# Pinscape_Pico_Expansion_Board_-_DIY_Frie.net
KiCad netlist of a schematic drawn in EAGLE
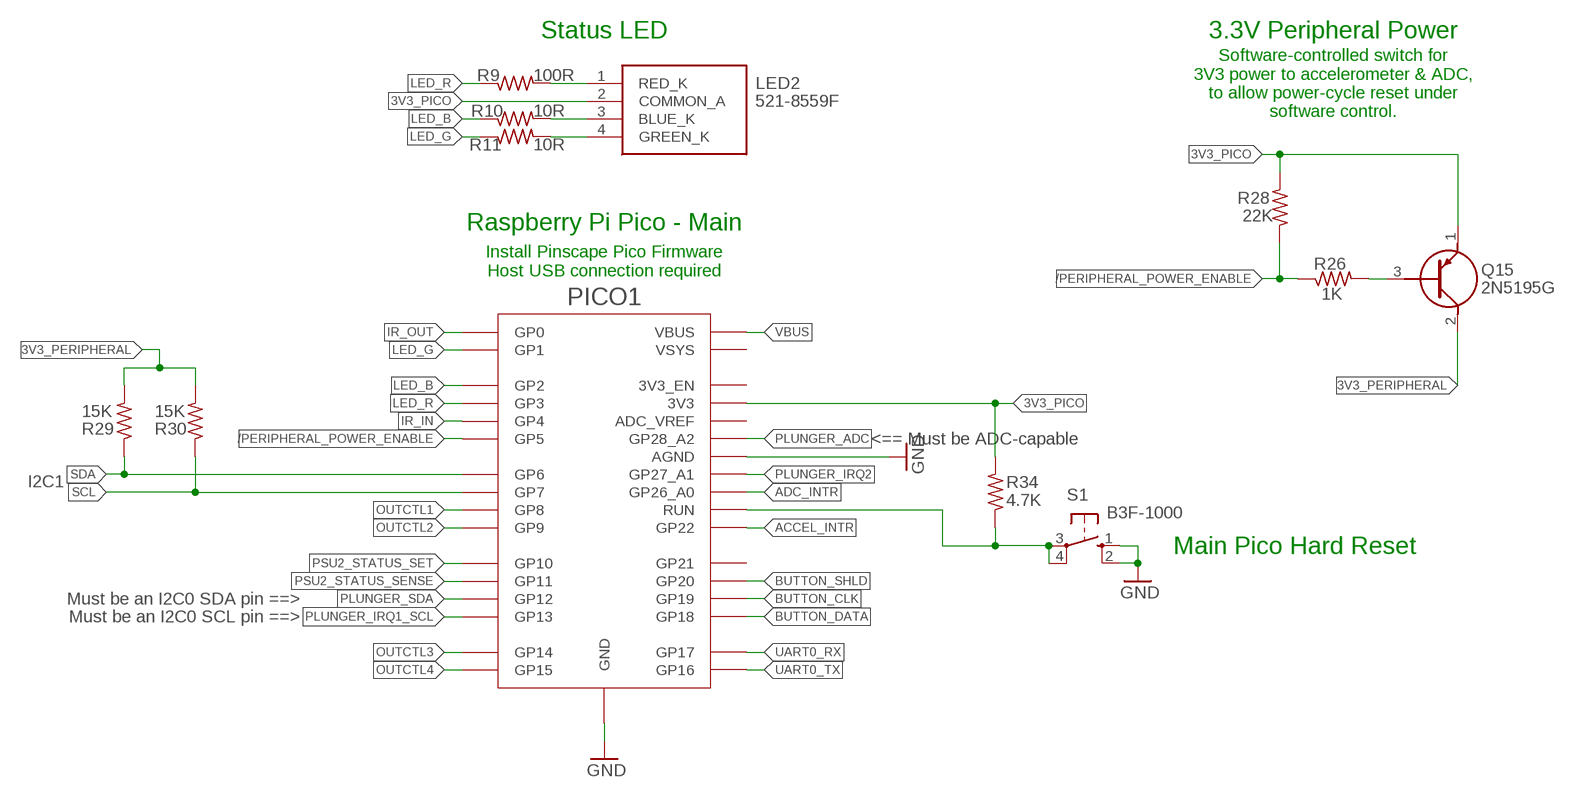
[diagram p0: schematic, sheet 1]
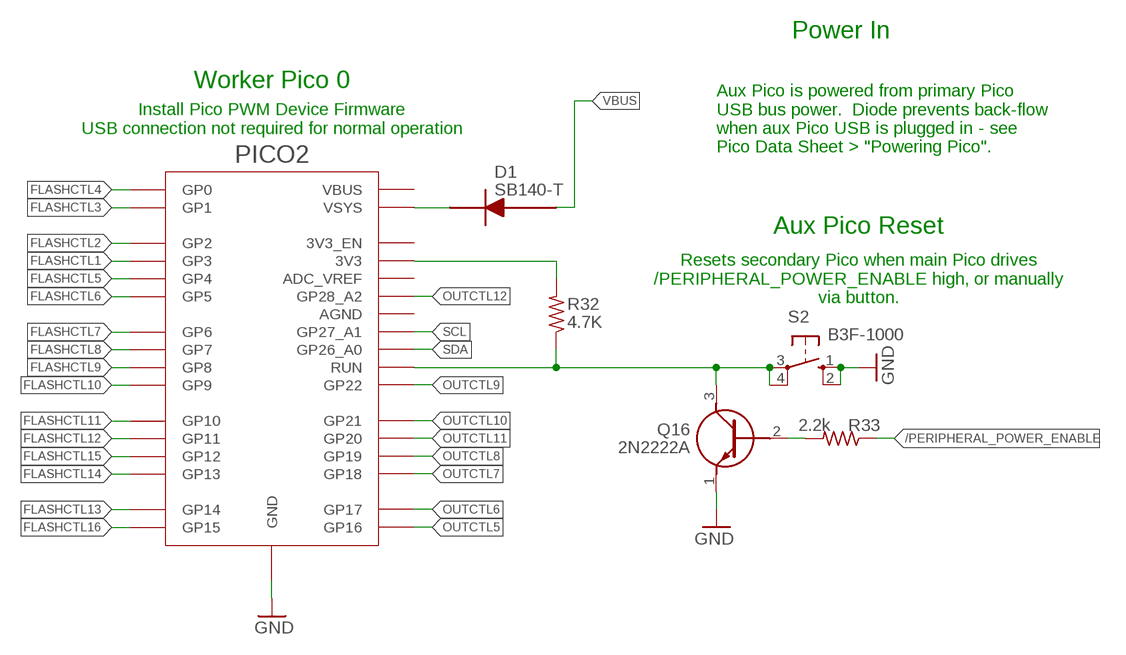
[diagram p1: schematic, sheet 2]
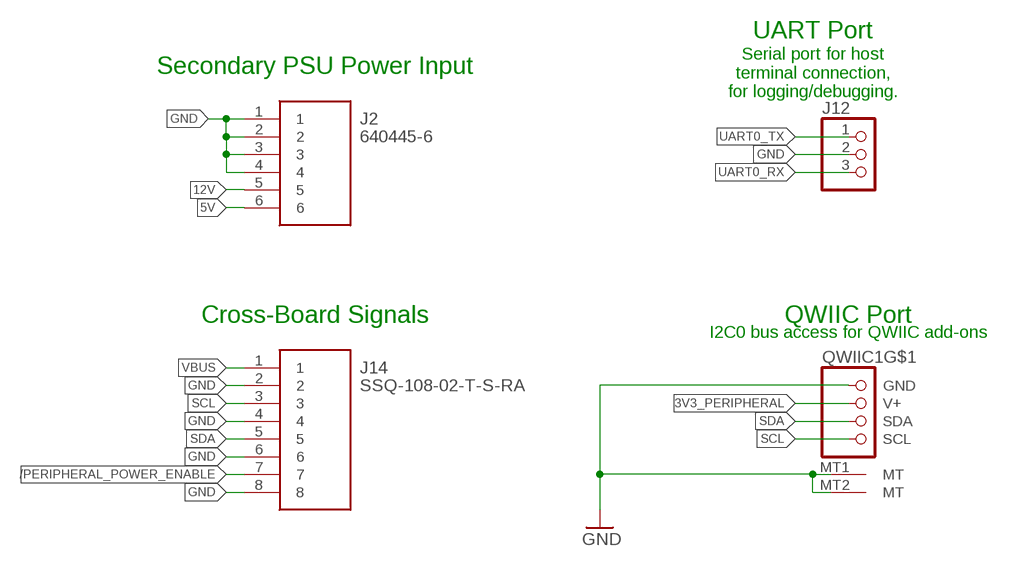
[diagram p2: schematic, sheet 3]
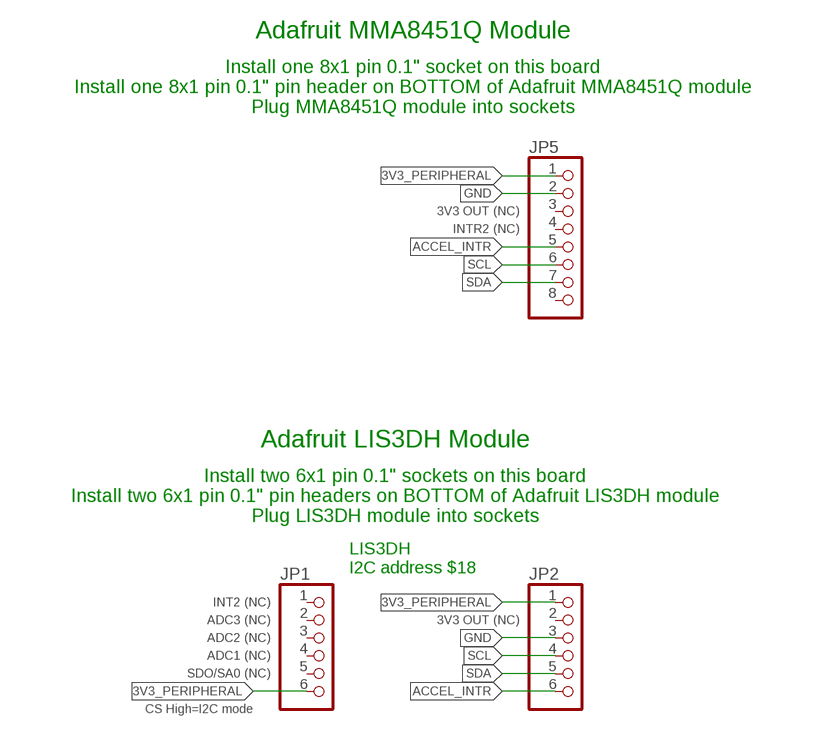
[diagram p3: schematic, sheet 4]
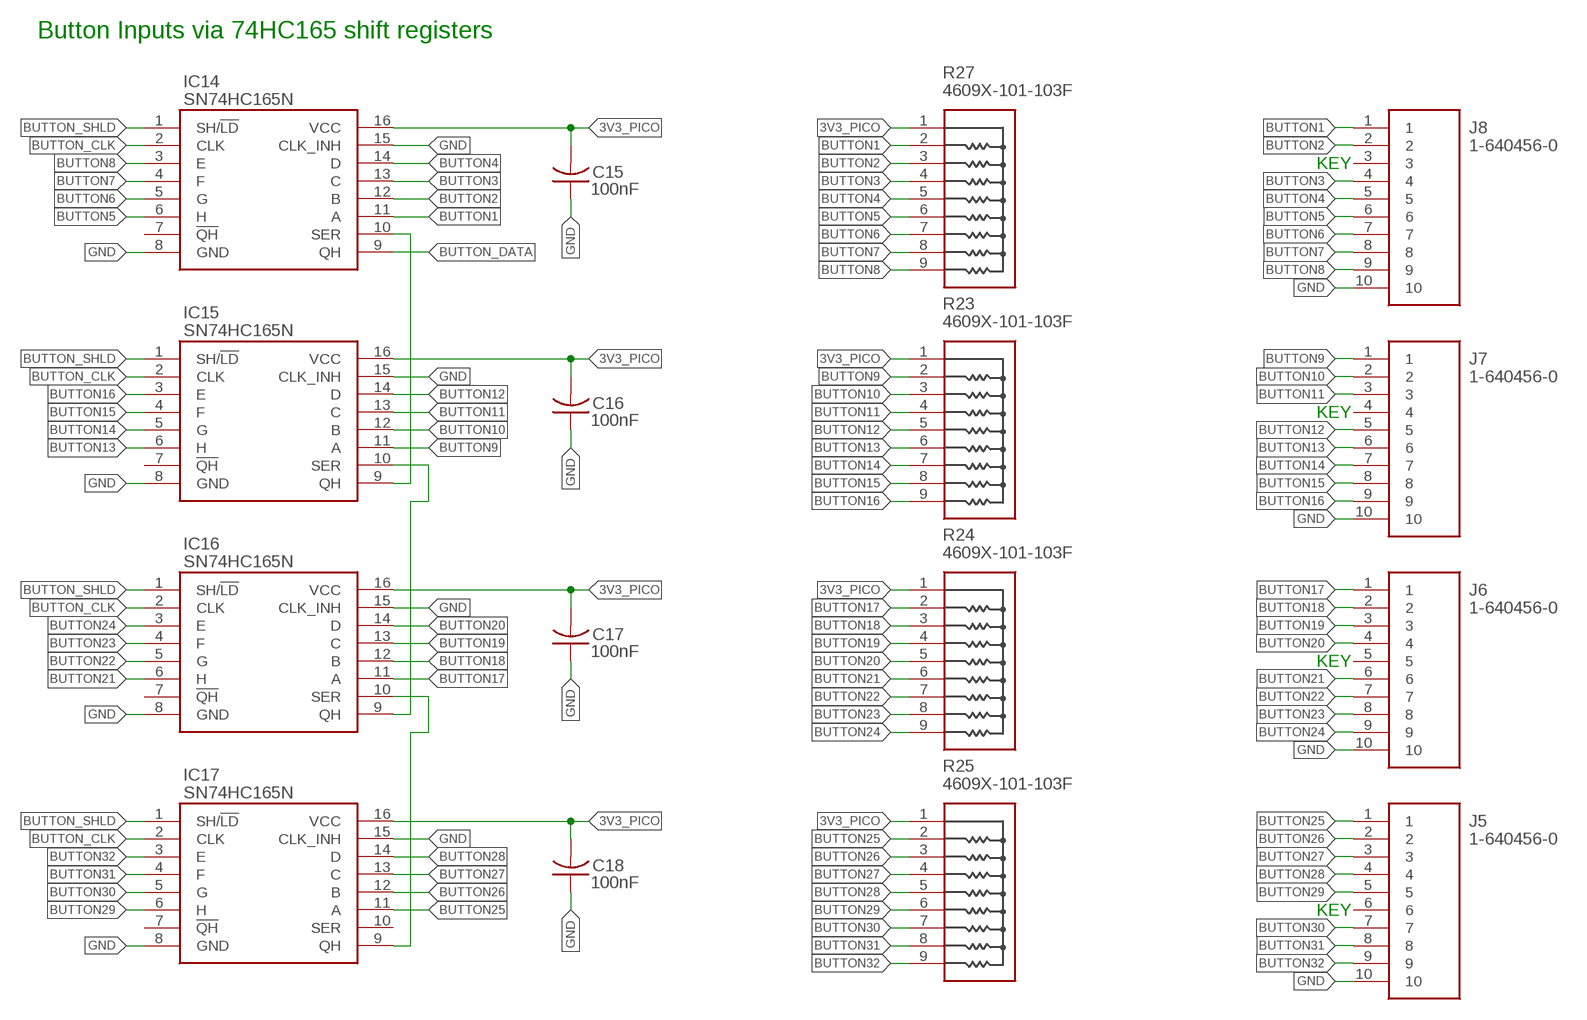
[diagram p4: schematic, sheet 5]
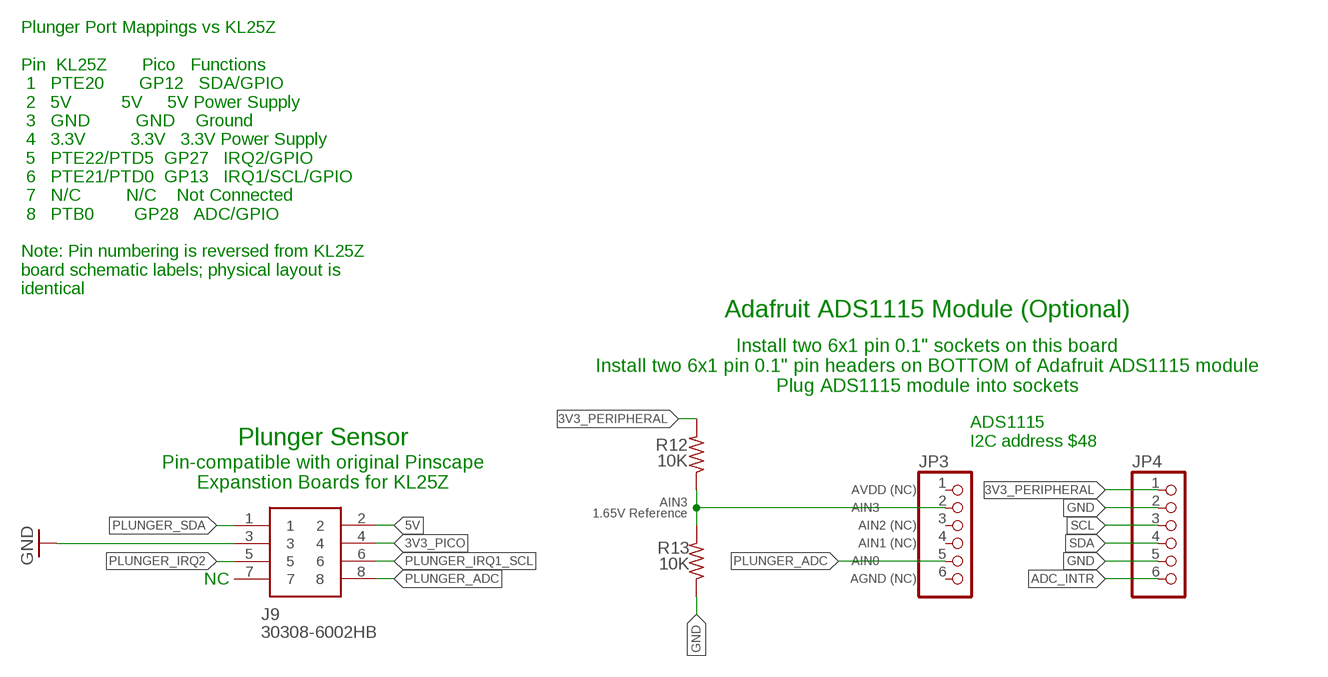
[diagram p5: schematic, sheet 6]
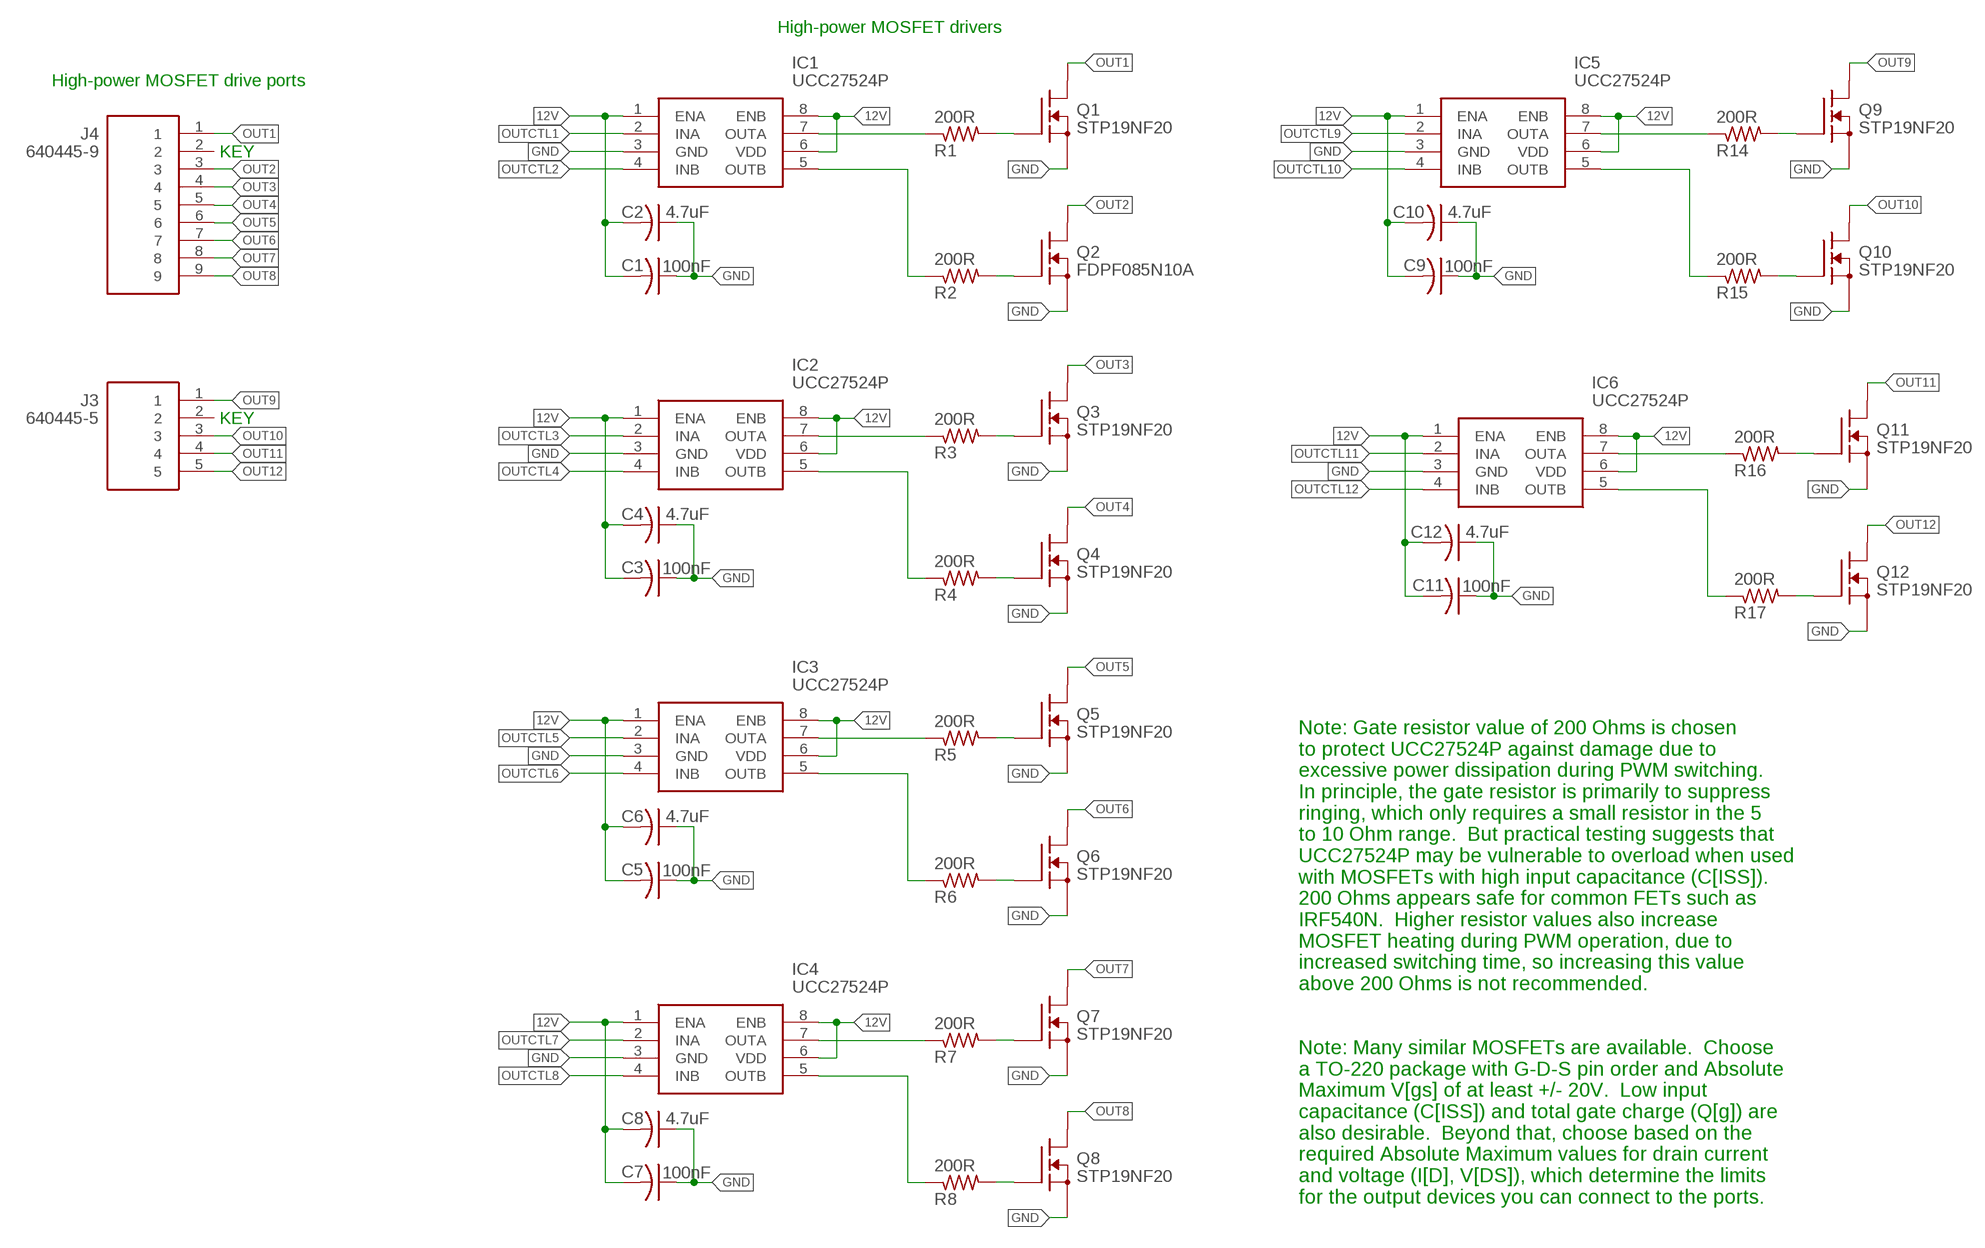
[diagram p6: schematic, sheet 7]
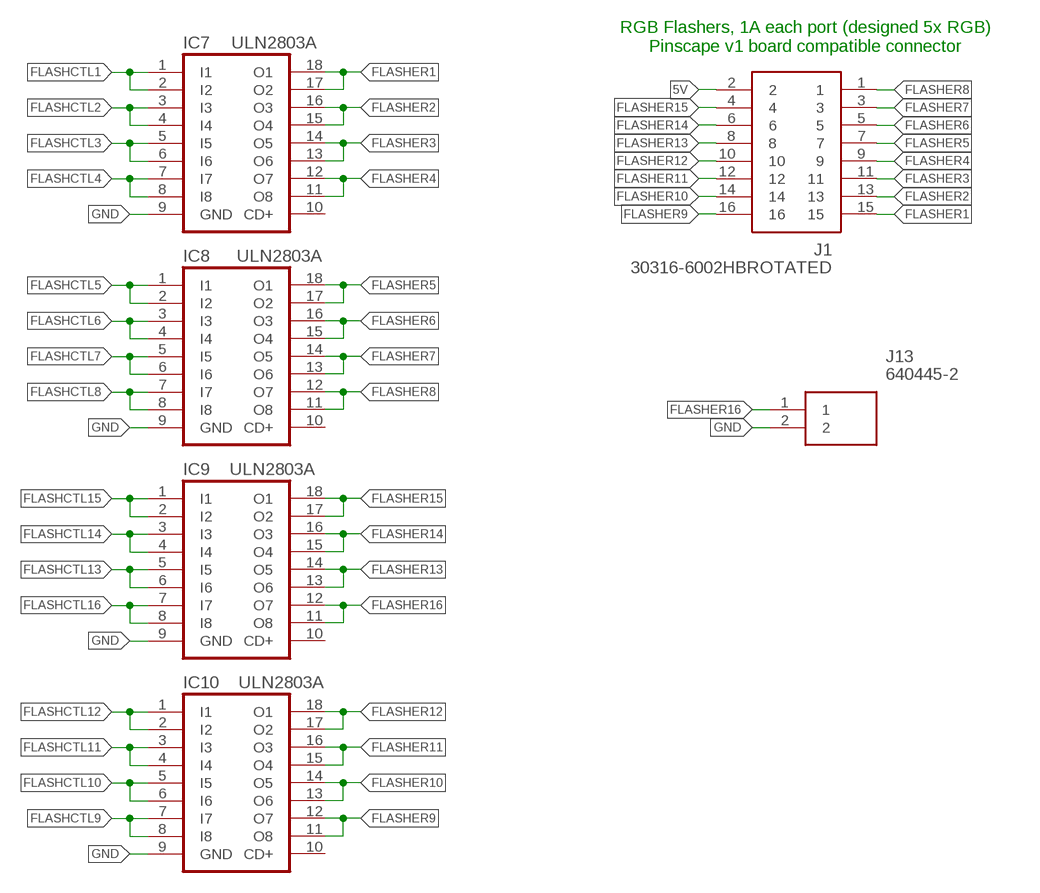
[diagram p7: schematic, sheet 8]
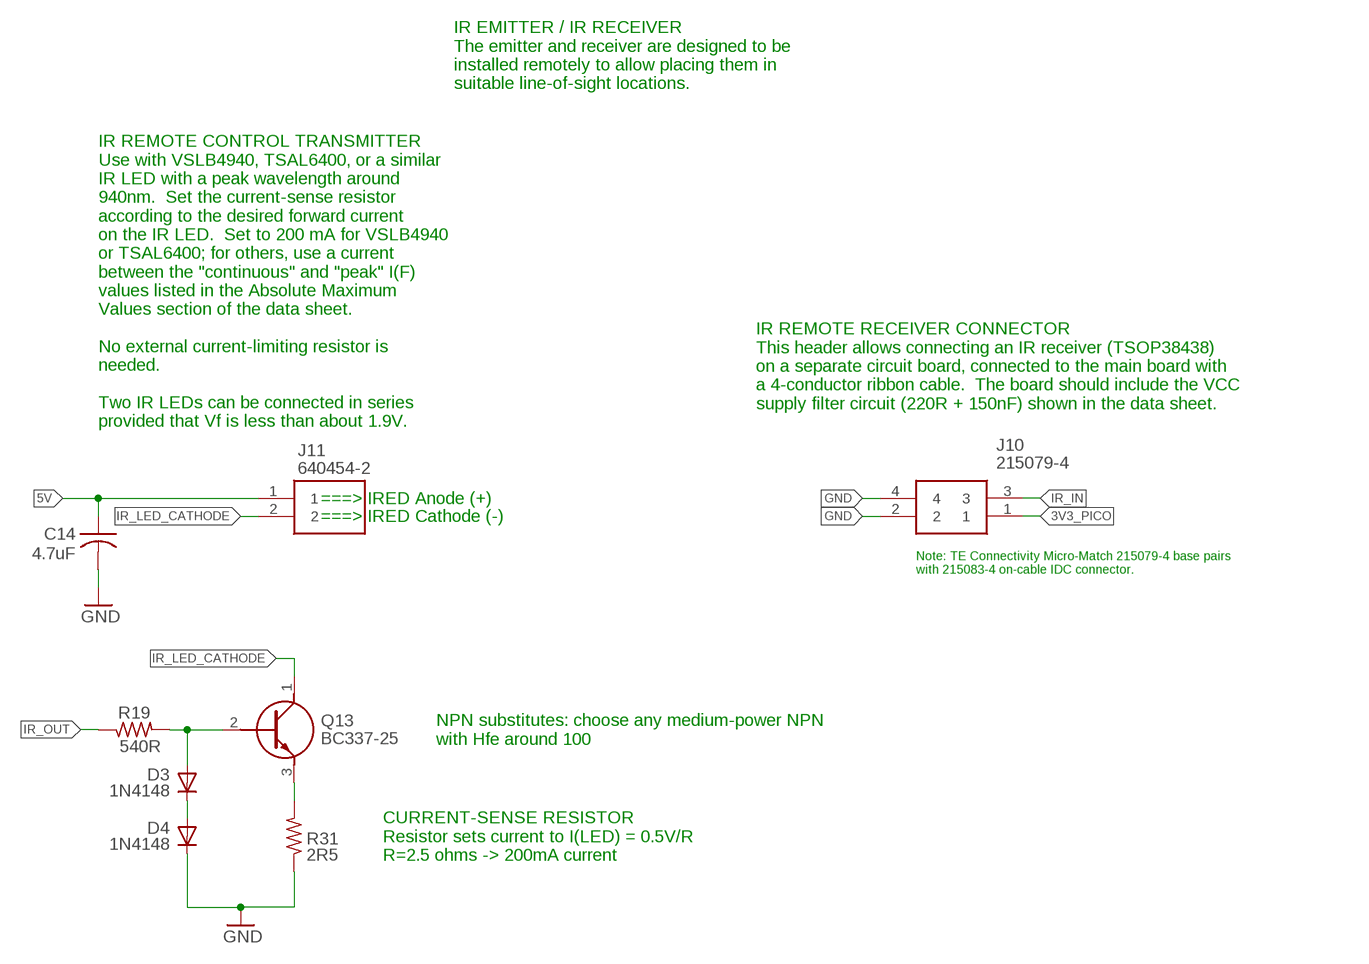
[diagram p8: schematic, sheet 9]
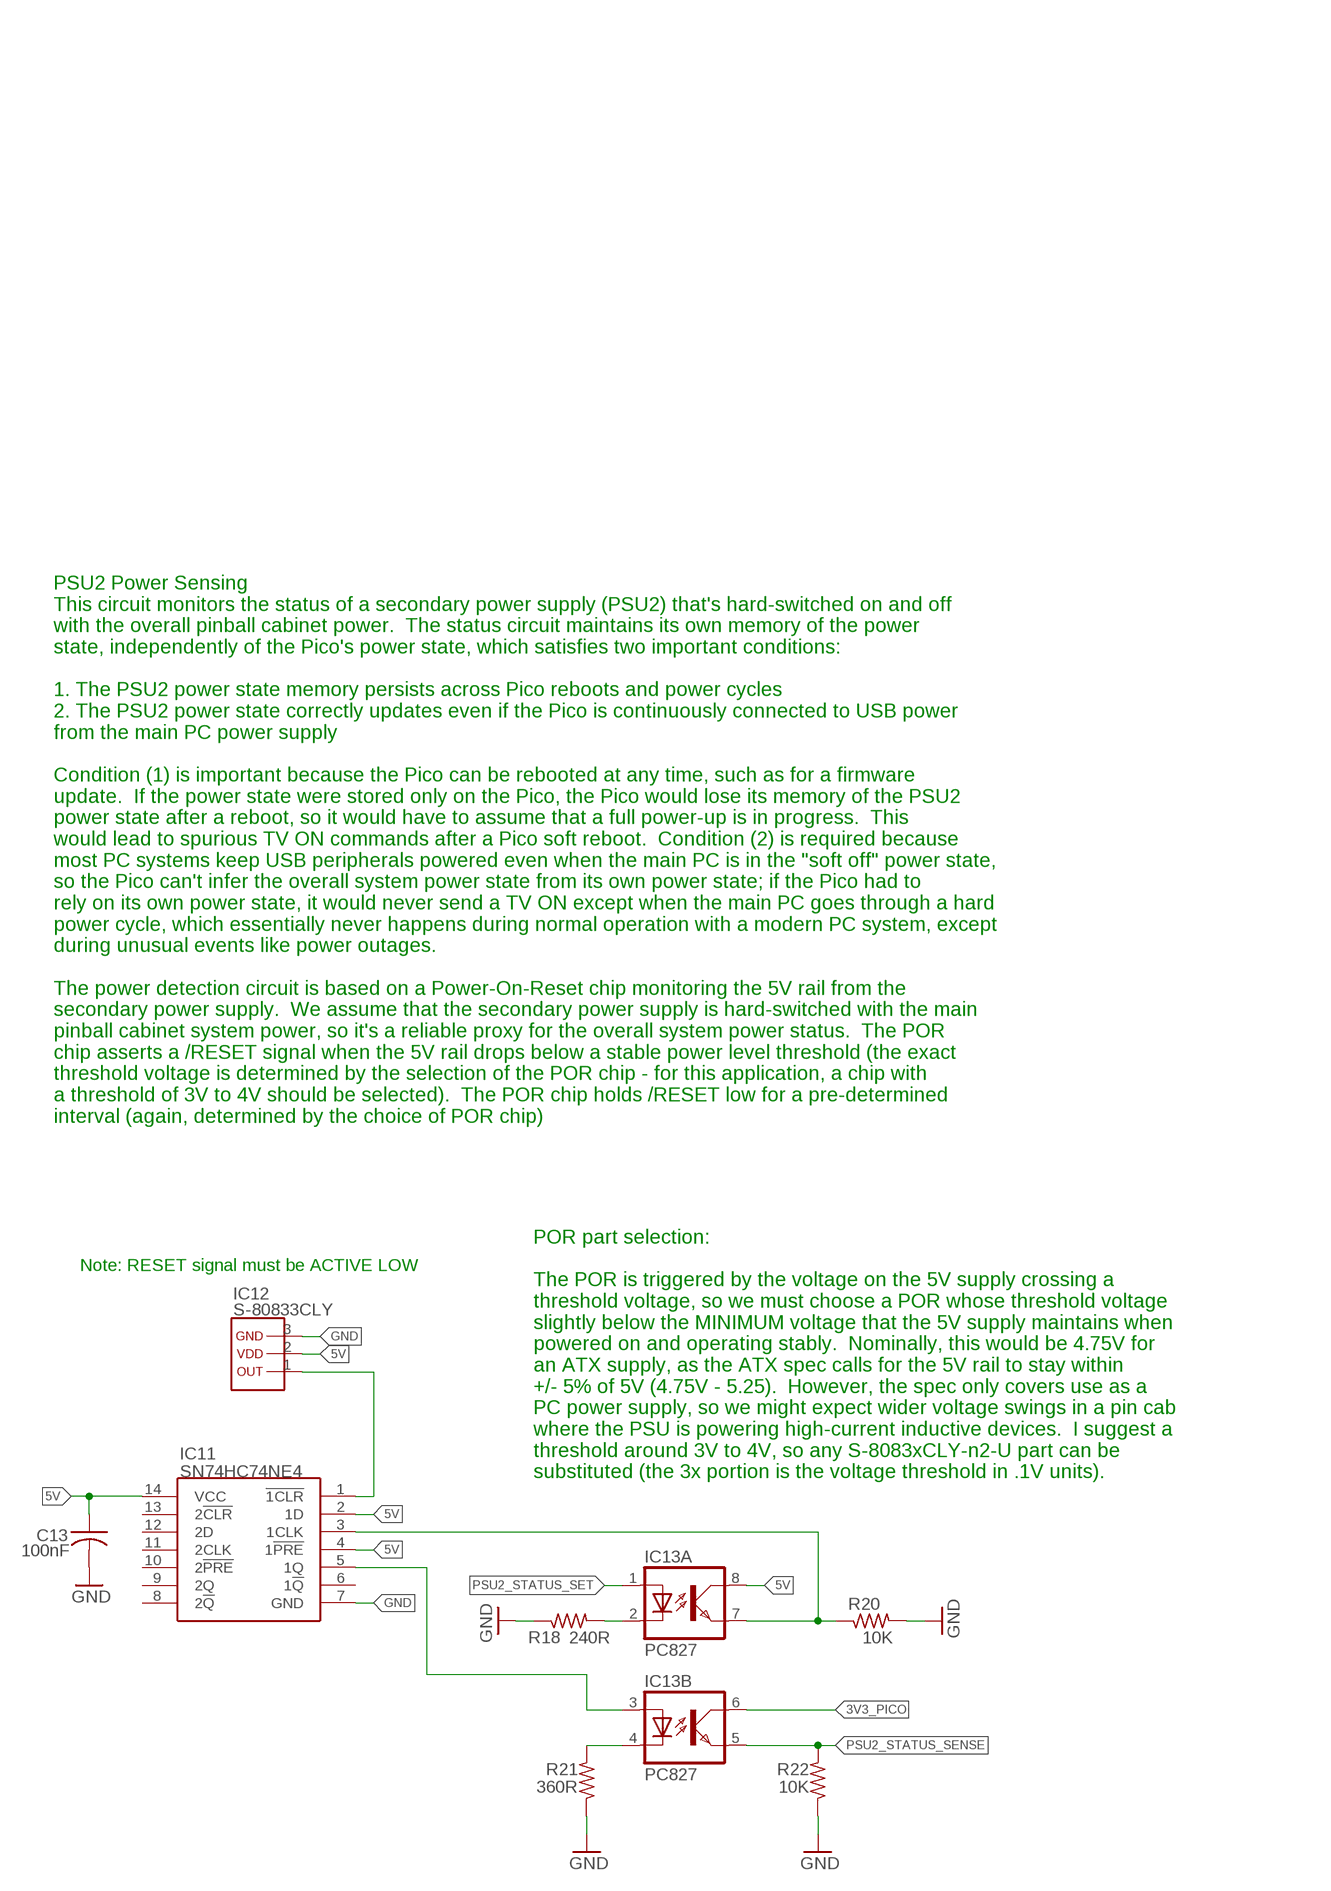
[diagram p9: schematic, sheet 10]
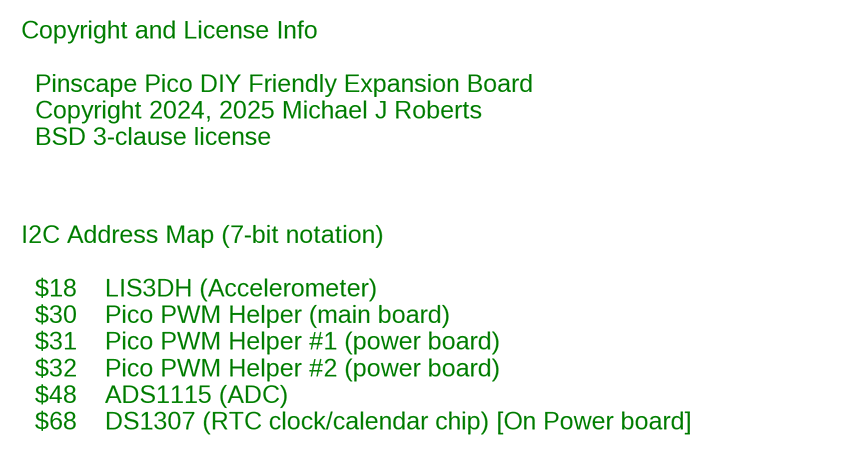
[diagram p10: schematic, sheet 11]

(export (version "E")
  (design (tool "Eeschema 10.0.6"))
  (components
    (comp (ref "IC7")
      (value "ULN2803A")
      (footprint "eagle-import:DIL18")
      (libsource (lib "eagle-import") (part "ULN2803A"))
    )
    (comp (ref "IC8")
      (value "ULN2803A")
      (footprint "eagle-import:DIL18")
      (libsource (lib "eagle-import") (part "ULN2803A"))
    )
    (comp (ref "IC9")
      (value "ULN2803A")
      (footprint "eagle-import:DIL18")
      (libsource (lib "eagle-import") (part "ULN2803A"))
    )
    (comp (ref "IC10")
      (value "ULN2803A")
      (footprint "eagle-import:DIL18")
      (libsource (lib "eagle-import") (part "ULN2803A"))
    )
    (comp (ref "J1")
      (value "30316-6002HBROTATED")
      (footprint "eagle-import:3M-30316-6002HB-ROTATED")
      (libsource (lib "eagle-import") (part "30316-6002HBROTATED"))
    )
    (comp (ref "J13")
      (value "640445-2")
      (footprint "eagle-import:SHDR2W117P0X396_1X2_792X762X11")
      (fields (field (name "MOUSER_PART_NUMBER") "5716404452"))
      (libsource (lib "eagle-import") (part "640445-2"))
    )
    (comp (ref "C13")
      (value "100nF")
      (footprint "eagle-import:C025-024X044")
      (fields (field (name "PARTNO") "K104K15X7RF5TL2"))
      (libsource (lib "eagle-import") (part "C-US025-024X044"))
    )
    (comp (ref "IC11")
      (value "SN74HC74NE4")
      (footprint "eagle-import:DIP794W53P254L1930H508Q14N")
      (fields (field (name "MOUSER_PART_NUMBER") "595-SN74HC74NE4"))
      (libsource (lib "eagle-import") (part "SN74HC74NE4"))
    )
    (comp (ref "IC12")
      (value "S-80833CLY")
      (footprint "eagle-import:TO-92_(TO-226)")
      (libsource (lib "eagle-import") (part "S-80833CLY-B2-UTO92"))
    )
    (comp (ref "IC13")
      (value "PC827")
      (footprint "eagle-import:DIL08")
      (libsource (lib "eagle-import") (part "PC827"))
    )
    (comp (ref "R18")
      (value "240R")
      (footprint "eagle-import:0204_7")
      (fields (field (name "PARTNO") "660-MFS1/4DCT52R47R0"))
      (libsource (lib "eagle-import") (part "R-US_0204/7"))
    )
    (comp (ref "R20")
      (value "10K")
      (footprint "eagle-import:0204_7")
      (fields (field (name "PARTNO") "mfr-12frrf52-10k"))
      (libsource (lib "eagle-import") (part "R-US_0204/7"))
    )
    (comp (ref "R21")
      (value "360R")
      (footprint "eagle-import:0204_7")
      (fields (field (name "PARTNO") "660-MFS1/4DCT52R47R0"))
      (libsource (lib "eagle-import") (part "R-US_0204/7"))
    )
    (comp (ref "R22")
      (value "10K")
      (footprint "eagle-import:0204_7")
      (fields (field (name "PARTNO") "mfr-12frrf52-10k"))
      (libsource (lib "eagle-import") (part "R-US_0204/7"))
    )
    (comp (ref "J2")
      (value "640445-6")
      (footprint "eagle-import:SHDR6W183P0X396_1X6_2377X762X1")
      (fields (field (name "MOUSER_PART_NUMBER") "571-6404456"))
      (libsource (lib "eagle-import") (part "640445-6"))
    )
    (comp (ref "J12")
      (value "PINHD-1X3")
      (footprint "eagle-import:1X03")
      (libsource (lib "eagle-import") (part "PINHD-1X3"))
    )
    (comp (ref "J14")
      (value "SSQ-108-02-T-S-RA")
      (footprint "eagle-import:RHDRRA8W64P254_1X8_2083X851X24")
      (fields (field (name "MOUSER_PART_NUMBER") "200-SSQ10802TSRA"))
      (libsource (lib "eagle-import") (part "SSQ-108-02-T-S-RA"))
    )
    (comp (ref "QWIIC1")
      (value "QWIIC")
      (footprint "eagle-import:JST_SH4")
      (libsource (lib "eagle-import") (part "STEMMA_I2C_QT"))
    )
    (comp (ref "JP1")
      (value "PINHD-1X6")
      (footprint "eagle-import:1X06")
      (libsource (lib "eagle-import") (part "PINHD-1X6"))
    )
    (comp (ref "JP2")
      (value "PINHD-1X6")
      (footprint "eagle-import:1X06")
      (libsource (lib "eagle-import") (part "PINHD-1X6"))
    )
    (comp (ref "JP5")
      (value "PINHD-1X8")
      (footprint "eagle-import:1X08")
      (libsource (lib "eagle-import") (part "PINHD-1X8"))
    )
    (comp (ref "J9")
      (value "30308-6002HB")
      (footprint "eagle-import:SHDR8W69P254_2X4_1780X878X955P")
      (libsource (lib "eagle-import") (part "30308-6002HB"))
    )
    (comp (ref "JP3")
      (value "PINHD-1X6")
      (footprint "eagle-import:1X06")
      (libsource (lib "eagle-import") (part "PINHD-1X6"))
    )
    (comp (ref "JP4")
      (value "PINHD-1X6")
      (footprint "eagle-import:1X06")
      (libsource (lib "eagle-import") (part "PINHD-1X6"))
    )
    (comp (ref "R12")
      (value "10K")
      (footprint "eagle-import:0204_7")
      (fields (field (name "PARTNO") "mfr-12frrf52-10k"))
      (libsource (lib "eagle-import") (part "R-US_0204/7"))
    )
    (comp (ref "R13")
      (value "10K")
      (footprint "eagle-import:0204_7")
      (fields (field (name "PARTNO") "mfr-12frrf52-10k"))
      (libsource (lib "eagle-import") (part "R-US_0204/7"))
    )
    (comp (ref "C1")
      (value "100nF")
      (footprint "eagle-import:C025-024X044")
      (fields (field (name "PARTNO") "K104K15X7RF5TL2"))
      (libsource (lib "eagle-import") (part "C-US025-024X044"))
    )
    (comp (ref "C2")
      (value "4.7uF")
      (footprint "eagle-import:C025-024X044")
      (fields (field (name "PARTNO") "810-FG14X5R1H475KRT0"))
      (libsource (lib "eagle-import") (part "C-US025-024X044"))
    )
    (comp (ref "C3")
      (value "100nF")
      (footprint "eagle-import:C025-024X044")
      (fields (field (name "PARTNO") "K104K15X7RF5TL2"))
      (libsource (lib "eagle-import") (part "C-US025-024X044"))
    )
    (comp (ref "C4")
      (value "4.7uF")
      (footprint "eagle-import:C025-024X044")
      (fields (field (name "PARTNO") "810-FG14X5R1H475KRT0"))
      (libsource (lib "eagle-import") (part "C-US025-024X044"))
    )
    (comp (ref "C5")
      (value "100nF")
      (footprint "eagle-import:C025-024X044")
      (fields (field (name "PARTNO") "K104K15X7RF5TL2"))
      (libsource (lib "eagle-import") (part "C-US025-024X044"))
    )
    (comp (ref "C6")
      (value "4.7uF")
      (footprint "eagle-import:C025-024X044")
      (fields (field (name "PARTNO") "810-FG14X5R1H475KRT0"))
      (libsource (lib "eagle-import") (part "C-US025-024X044"))
    )
    (comp (ref "C7")
      (value "100nF")
      (footprint "eagle-import:C025-024X044")
      (fields (field (name "PARTNO") "K104K15X7RF5TL2"))
      (libsource (lib "eagle-import") (part "C-US025-024X044"))
    )
    (comp (ref "C8")
      (value "4.7uF")
      (footprint "eagle-import:C025-024X044")
      (fields (field (name "PARTNO") "810-FG14X5R1H475KRT0"))
      (libsource (lib "eagle-import") (part "C-US025-024X044"))
    )
    (comp (ref "C9")
      (value "100nF")
      (footprint "eagle-import:C025-024X044")
      (fields (field (name "PARTNO") "K104K15X7RF5TL2"))
      (libsource (lib "eagle-import") (part "C-US025-024X044"))
    )
    (comp (ref "C10")
      (value "4.7uF")
      (footprint "eagle-import:C025-024X044")
      (fields (field (name "PARTNO") "810-FG14X5R1H475KRT0"))
      (libsource (lib "eagle-import") (part "C-US025-024X044"))
    )
    (comp (ref "C11")
      (value "100nF")
      (footprint "eagle-import:C025-024X044")
      (fields (field (name "PARTNO") "K104K15X7RF5TL2"))
      (libsource (lib "eagle-import") (part "C-US025-024X044"))
    )
    (comp (ref "C12")
      (value "4.7uF")
      (footprint "eagle-import:C025-024X044")
      (fields (field (name "PARTNO") "810-FG14X5R1H475KRT0"))
      (libsource (lib "eagle-import") (part "C-US025-024X044"))
    )
    (comp (ref "IC1")
      (value "UCC27524P")
      (footprint "eagle-import:DIP794W53P254L959H508Q8N")
      (fields (field (name "MOUSER_PART_NUMBER") "595-UCC27524P"))
      (libsource (lib "eagle-import") (part "UCC27524P"))
    )
    (comp (ref "IC2")
      (value "UCC27524P")
      (footprint "eagle-import:DIP794W53P254L959H508Q8N")
      (fields (field (name "MOUSER_PART_NUMBER") "595-UCC27524P"))
      (libsource (lib "eagle-import") (part "UCC27524P"))
    )
    (comp (ref "IC3")
      (value "UCC27524P")
      (footprint "eagle-import:DIP794W53P254L959H508Q8N")
      (fields (field (name "MOUSER_PART_NUMBER") "595-UCC27524P"))
      (libsource (lib "eagle-import") (part "UCC27524P"))
    )
    (comp (ref "IC4")
      (value "UCC27524P")
      (footprint "eagle-import:DIP794W53P254L959H508Q8N")
      (fields (field (name "MOUSER_PART_NUMBER") "595-UCC27524P"))
      (libsource (lib "eagle-import") (part "UCC27524P"))
    )
    (comp (ref "IC5")
      (value "UCC27524P")
      (footprint "eagle-import:DIP794W53P254L959H508Q8N")
      (fields (field (name "MOUSER_PART_NUMBER") "595-UCC27524P"))
      (libsource (lib "eagle-import") (part "UCC27524P"))
    )
    (comp (ref "IC6")
      (value "UCC27524P")
      (footprint "eagle-import:DIP794W53P254L959H508Q8N")
      (fields (field (name "MOUSER_PART_NUMBER") "595-UCC27524P"))
      (libsource (lib "eagle-import") (part "UCC27524P"))
    )
    (comp (ref "J3")
      (value "640445-5")
      (footprint "eagle-import:HDRV5W117P0X396_1X5_1981X762X1")
      (fields (field (name "MOUSER_PART_NUMBER") "571-640445-5"))
      (libsource (lib "eagle-import") (part "640445-5"))
    )
    (comp (ref "J4")
      (value "640445-9")
      (footprint "eagle-import:SHDR9W117P0X396_1X9_3566X762X1")
      (fields (field (name "MOUSER_PART_NUMBER") "571-6404459"))
      (libsource (lib "eagle-import") (part "640445-9"))
    )
    (comp (ref "Q1")
      (value "STP19NF20")
      (footprint "eagle-import:TO220BV")
      (fields (field (name "PARTNO") "FDPF085N10A"))
      (libsource (lib "eagle-import") (part "BUK7575-55A"))
    )
    (comp (ref "Q2")
      (value "FDPF085N10A")
      (footprint "eagle-import:TO220BV")
      (fields (field (name "PARTNO") "FDPF085N10A"))
      (libsource (lib "eagle-import") (part "BUK7575-55A"))
    )
    (comp (ref "Q3")
      (value "STP19NF20")
      (footprint "eagle-import:TO220BV")
      (fields (field (name "PARTNO") "FDPF085N10A"))
      (libsource (lib "eagle-import") (part "BUK7575-55A"))
    )
    (comp (ref "Q4")
      (value "STP19NF20")
      (footprint "eagle-import:TO220BV")
      (fields (field (name "PARTNO") "FDPF085N10A"))
      (libsource (lib "eagle-import") (part "BUK7575-55A"))
    )
    (comp (ref "Q5")
      (value "STP19NF20")
      (footprint "eagle-import:TO220BV")
      (fields (field (name "PARTNO") "FDPF085N10A"))
      (libsource (lib "eagle-import") (part "BUK7575-55A"))
    )
    (comp (ref "Q6")
      (value "STP19NF20")
      (footprint "eagle-import:TO220BV")
      (fields (field (name "PARTNO") "FDPF085N10A"))
      (libsource (lib "eagle-import") (part "BUK7575-55A"))
    )
    (comp (ref "Q7")
      (value "STP19NF20")
      (footprint "eagle-import:TO220BV")
      (fields (field (name "PARTNO") "FDPF085N10A"))
      (libsource (lib "eagle-import") (part "BUK7575-55A"))
    )
    (comp (ref "Q8")
      (value "STP19NF20")
      (footprint "eagle-import:TO220BV")
      (fields (field (name "PARTNO") "FDPF085N10A"))
      (libsource (lib "eagle-import") (part "BUK7575-55A"))
    )
    (comp (ref "Q9")
      (value "STP19NF20")
      (footprint "eagle-import:TO220BV")
      (fields (field (name "PARTNO") "FDPF085N10A"))
      (libsource (lib "eagle-import") (part "BUK7575-55A"))
    )
    (comp (ref "Q10")
      (value "STP19NF20")
      (footprint "eagle-import:TO220BV")
      (fields (field (name "PARTNO") "FDPF085N10A"))
      (libsource (lib "eagle-import") (part "BUK7575-55A"))
    )
    (comp (ref "Q11")
      (value "STP19NF20")
      (footprint "eagle-import:TO220BV")
      (fields (field (name "PARTNO") "FDPF085N10A"))
      (libsource (lib "eagle-import") (part "BUK7575-55A"))
    )
    (comp (ref "Q12")
      (value "STP19NF20")
      (footprint "eagle-import:TO220BV")
      (fields (field (name "PARTNO") "FDPF085N10A"))
      (libsource (lib "eagle-import") (part "BUK7575-55A"))
    )
    (comp (ref "R1")
      (value "200R")
      (footprint "eagle-import:0204_5")
      (fields (field (name "PARTNO") "660-MFS1/4DCT52R47R0"))
      (libsource (lib "eagle-import") (part "R-US_0204/5"))
    )
    (comp (ref "R2")
      (value "200R")
      (footprint "eagle-import:0204_5")
      (fields (field (name "PARTNO") "660-MFS1/4DCT52R47R0"))
      (libsource (lib "eagle-import") (part "R-US_0204/5"))
    )
    (comp (ref "R3")
      (value "200R")
      (footprint "eagle-import:0204_5")
      (fields (field (name "PARTNO") "660-MFS1/4DCT52R47R0"))
      (libsource (lib "eagle-import") (part "R-US_0204/5"))
    )
    (comp (ref "R4")
      (value "200R")
      (footprint "eagle-import:0204_5")
      (fields (field (name "PARTNO") "660-MFS1/4DCT52R47R0"))
      (libsource (lib "eagle-import") (part "R-US_0204/5"))
    )
    (comp (ref "R5")
      (value "200R")
      (footprint "eagle-import:0204_5")
      (fields (field (name "PARTNO") "660-MFS1/4DCT52R47R0"))
      (libsource (lib "eagle-import") (part "R-US_0204/5"))
    )
    (comp (ref "R6")
      (value "200R")
      (footprint "eagle-import:0204_5")
      (fields (field (name "PARTNO") "660-MFS1/4DCT52R47R0"))
      (libsource (lib "eagle-import") (part "R-US_0204/5"))
    )
    (comp (ref "R7")
      (value "200R")
      (footprint "eagle-import:0204_5")
      (fields (field (name "PARTNO") "660-MFS1/4DCT52R47R0"))
      (libsource (lib "eagle-import") (part "R-US_0204/5"))
    )
    (comp (ref "R8")
      (value "200R")
      (footprint "eagle-import:0204_5")
      (fields (field (name "PARTNO") "660-MFS1/4DCT52R47R0"))
      (libsource (lib "eagle-import") (part "R-US_0204/5"))
    )
    (comp (ref "R14")
      (value "200R")
      (footprint "eagle-import:0204_5")
      (fields (field (name "PARTNO") "660-MFS1/4DCT52R47R0"))
      (libsource (lib "eagle-import") (part "R-US_0204/5"))
    )
    (comp (ref "R15")
      (value "200R")
      (footprint "eagle-import:0204_5")
      (fields (field (name "PARTNO") "660-MFS1/4DCT52R47R0"))
      (libsource (lib "eagle-import") (part "R-US_0204/5"))
    )
    (comp (ref "R16")
      (value "200R")
      (footprint "eagle-import:0204_5")
      (fields (field (name "PARTNO") "660-MFS1/4DCT52R47R0"))
      (libsource (lib "eagle-import") (part "R-US_0204/5"))
    )
    (comp (ref "R17")
      (value "200R")
      (footprint "eagle-import:0204_5")
      (fields (field (name "PARTNO") "660-MFS1/4DCT52R47R0"))
      (libsource (lib "eagle-import") (part "R-US_0204/5"))
    )
    (comp (ref "LED2")
      (value "521-8559F")
      (footprint "eagle-import:5218559F")
      (fields (field (name "MOUSER_PART_NUMBER") "645-5218559F"))
      (libsource (lib "eagle-import") (part "521-8559F"))
    )
    (comp (ref "PICO1")
      (value "RPI_PICO_NO_DEBUG")
      (footprint "eagle-import:RPI_PICO_TH_NO_DEBUG")
      (libsource (lib "eagle-import") (part "RPI_PICO_NO_DEBUG"))
    )
    (comp (ref "Q15")
      (value "2N5195G")
      (footprint "eagle-import:TO229P300X760X1364-3P")
      (fields (field (name "MOUSER_PART_NUMBER") "863-2N5195G"))
      (libsource (lib "eagle-import") (part "2N5195G"))
    )
    (comp (ref "R9")
      (value "100R")
      (footprint "eagle-import:0204_7")
      (fields (field (name "PARTNO") "MFR-12FTE52-100R"))
      (libsource (lib "eagle-import") (part "R-US_0204/7"))
    )
    (comp (ref "R10")
      (value "10R")
      (footprint "eagle-import:0204_7")
      (fields (field (name "PARTNO") "MFR25SFTE52-10R"))
      (libsource (lib "eagle-import") (part "R-US_0204/7"))
    )
    (comp (ref "R11")
      (value "10R")
      (footprint "eagle-import:0204_7")
      (fields (field (name "PARTNO") "MFR25SFTE52-10R"))
      (libsource (lib "eagle-import") (part "R-US_0204/7"))
    )
    (comp (ref "R26")
      (value "1K")
      (footprint "eagle-import:0204_7")
      (fields (field (name "PARTNO") "MF0204FTE52-1K"))
      (libsource (lib "eagle-import") (part "R-US_0204/7"))
    )
    (comp (ref "R28")
      (value "22K")
      (footprint "eagle-import:0204_7")
      (fields (field (name "PARTNO") "660-MFS1/4DCT52R47R0"))
      (libsource (lib "eagle-import") (part "R-US_0204/7"))
    )
    (comp (ref "R29")
      (value "15K")
      (footprint "eagle-import:0204_7")
      (fields (field (name "PARTNO") "MFR25SFRF52-15K"))
      (libsource (lib "eagle-import") (part "R-US_0204/7"))
    )
    (comp (ref "R30")
      (value "15K")
      (footprint "eagle-import:0204_7")
      (fields (field (name "PARTNO") "MFR25SFRF52-15K"))
      (libsource (lib "eagle-import") (part "R-US_0204/7"))
    )
    (comp (ref "R34")
      (value "4.7K")
      (footprint "eagle-import:0204_7")
      (fields (field (name "PARTNO") "660-MFS1/4DCT52R47R0"))
      (libsource (lib "eagle-import") (part "R-US_0204/7"))
    )
    (comp (ref "S1")
      (value "B3F-1000")
      (footprint "eagle-import:B3F-10XX")
      (libsource (lib "eagle-import") (part "10-XX"))
    )
    (comp (ref "C15")
      (value "100nF")
      (footprint "eagle-import:C025-024X044")
      (fields (field (name "PARTNO") "K104K15X7RF5TL2"))
      (libsource (lib "eagle-import") (part "C-US025-024X044"))
    )
    (comp (ref "C16")
      (value "100nF")
      (footprint "eagle-import:C025-024X044")
      (fields (field (name "PARTNO") "K104K15X7RF5TL2"))
      (libsource (lib "eagle-import") (part "C-US025-024X044"))
    )
    (comp (ref "C17")
      (value "100nF")
      (footprint "eagle-import:C025-024X044")
      (fields (field (name "PARTNO") "K104K15X7RF5TL2"))
      (libsource (lib "eagle-import") (part "C-US025-024X044"))
    )
    (comp (ref "C18")
      (value "100nF")
      (footprint "eagle-import:C025-024X044")
      (fields (field (name "PARTNO") "K104K15X7RF5TL2"))
      (libsource (lib "eagle-import") (part "C-US025-024X044"))
    )
    (comp (ref "IC14")
      (value "SN74HC165N")
      (footprint "eagle-import:DIP794W53P254L1930H508Q16N")
      (fields (field (name "MOUSER_PART_NUMBER") "595-SN74HC165N"))
      (libsource (lib "eagle-import") (part "SN74HC165N"))
    )
    (comp (ref "IC15")
      (value "SN74HC165N")
      (footprint "eagle-import:DIP794W53P254L1930H508Q16N")
      (fields (field (name "MOUSER_PART_NUMBER") "595-SN74HC165N"))
      (libsource (lib "eagle-import") (part "SN74HC165N"))
    )
    (comp (ref "IC16")
      (value "SN74HC165N")
      (footprint "eagle-import:DIP794W53P254L1930H508Q16N")
      (fields (field (name "MOUSER_PART_NUMBER") "595-SN74HC165N"))
      (libsource (lib "eagle-import") (part "SN74HC165N"))
    )
    (comp (ref "IC17")
      (value "SN74HC165N")
      (footprint "eagle-import:DIP794W53P254L1930H508Q16N")
      (fields (field (name "MOUSER_PART_NUMBER") "595-SN74HC165N"))
      (libsource (lib "eagle-import") (part "SN74HC165N"))
    )
    (comp (ref "J5")
      (value "1-640456-0")
      (footprint "eagle-import:SHDR10W66P0X254_1X10_2540X572X")
      (fields (field (name "MOUSER_PART_NUMBER") "571-16404560"))
      (libsource (lib "eagle-import") (part "1-640456-0"))
    )
    (comp (ref "J6")
      (value "1-640456-0")
      (footprint "eagle-import:SHDR10W66P0X254_1X10_2540X572X")
      (fields (field (name "MOUSER_PART_NUMBER") "571-16404560"))
      (libsource (lib "eagle-import") (part "1-640456-0"))
    )
    (comp (ref "J7")
      (value "1-640456-0")
      (footprint "eagle-import:SHDR10W66P0X254_1X10_2540X572X")
      (fields (field (name "MOUSER_PART_NUMBER") "571-16404560"))
      (libsource (lib "eagle-import") (part "1-640456-0"))
    )
    (comp (ref "J8")
      (value "1-640456-0")
      (footprint "eagle-import:SHDR10W66P0X254_1X10_2540X572X")
      (fields (field (name "MOUSER_PART_NUMBER") "571-16404560"))
      (libsource (lib "eagle-import") (part "1-640456-0"))
    )
    (comp (ref "R23")
      (value "4609X-101-103F")
      (footprint "eagle-import:4609X")
      (fields
        (field (name "MANUFACTURER_PART_NUMBER") "4609X-101-122LF")
        (field (name "MOUSER_PART_NUMBER") "652-4609X-1LF-1.2K")
      )
      (libsource (lib "eagle-import") (part "4609X-101-122LF"))
    )
    (comp (ref "R24")
      (value "4609X-101-103F")
      (footprint "eagle-import:4609X")
      (fields
        (field (name "MANUFACTURER_PART_NUMBER") "4609X-101-122LF")
        (field (name "MOUSER_PART_NUMBER") "652-4609X-1LF-1.2K")
      )
      (libsource (lib "eagle-import") (part "4609X-101-122LF"))
    )
    (comp (ref "R25")
      (value "4609X-101-103F")
      (footprint "eagle-import:4609X")
      (fields
        (field (name "MANUFACTURER_PART_NUMBER") "4609X-101-122LF")
        (field (name "MOUSER_PART_NUMBER") "652-4609X-1LF-1.2K")
      )
      (libsource (lib "eagle-import") (part "4609X-101-122LF"))
    )
    (comp (ref "R27")
      (value "4609X-101-103F")
      (footprint "eagle-import:4609X")
      (fields
        (field (name "MANUFACTURER_PART_NUMBER") "4609X-101-122LF")
        (field (name "MOUSER_PART_NUMBER") "652-4609X-1LF-1.2K")
      )
      (libsource (lib "eagle-import") (part "4609X-101-122LF"))
    )
    (comp (ref "D1")
      (value "SB140-T")
      (footprint "eagle-import:DIOAD1408W86L464D236")
      (fields (field (name "MOUSER_PART_NUMBER") "621-SB140-T"))
      (libsource (lib "eagle-import") (part "SB140-T"))
    )
    (comp (ref "PICO2")
      (value "RPI_PICO_NO_DEBUG")
      (footprint "eagle-import:RPI_PICO_TH_NO_DEBUG")
      (libsource (lib "eagle-import") (part "RPI_PICO_NO_DEBUG"))
    )
    (comp (ref "Q16")
      (value "2N2222A")
      (footprint "eagle-import:2N2222A")
      (fields (field (name "MOUSER_PART_NUMBER") "637-2N2222A"))
      (libsource (lib "eagle-import") (part "2N2222A"))
    )
    (comp (ref "R32")
      (value "4.7K")
      (footprint "eagle-import:0204_7")
      (fields (field (name "PARTNO") "660-MFS1/4DCT52R47R0"))
      (libsource (lib "eagle-import") (part "R-US_0204/7"))
    )
    (comp (ref "R33")
      (value "2.2k")
      (footprint "eagle-import:0204_7")
      (fields (field (name "PARTNO") "660-MFS1/4DCT52R47R0"))
      (libsource (lib "eagle-import") (part "R-US_0204/7"))
    )
    (comp (ref "S2")
      (value "B3F-1000")
      (footprint "eagle-import:B3F-10XX")
      (libsource (lib "eagle-import") (part "10-XX"))
    )
    (comp (ref "C14")
      (value "4.7uF")
      (footprint "eagle-import:C025-024X044")
      (fields (field (name "PARTNO") "810-FG14X5R1H475KRT0"))
      (libsource (lib "eagle-import") (part "C-US025-024X044"))
    )
    (comp (ref "D3")
      (value "1N4148")
      (footprint "eagle-import:DO35-7")
      (libsource (lib "eagle-import") (part "1N4148DO35-7"))
    )
    (comp (ref "D4")
      (value "1N4148")
      (footprint "eagle-import:DO35-7")
      (libsource (lib "eagle-import") (part "1N4148DO35-7"))
    )
    (comp (ref "J10")
      (value "215079-4")
      (footprint "eagle-import:2150794")
      (fields (field (name "MOUSER_PART_NUMBER") "571-215079-4"))
      (libsource (lib "eagle-import") (part "215079-4"))
    )
    (comp (ref "J11")
      (value "640454-2")
      (footprint "eagle-import:HDRV2W66P0X254_1X2_762X572X100")
      (fields (field (name "MOUSER_PART_NUMBER") "571-640454-2"))
      (libsource (lib "eagle-import") (part "640454-2"))
    )
    (comp (ref "Q13")
      (value "BC337-25")
      (footprint "eagle-import:BC33725")
      (fields (field (name "MOUSER_PART_NUMBER") "637-BC337-25"))
      (libsource (lib "eagle-import") (part "BC337-25"))
    )
    (comp (ref "R19")
      (value "540R")
      (footprint "eagle-import:0204_7")
      (fields (field (name "PARTNO") "660-MFS1/4DCT52R47R0"))
      (libsource (lib "eagle-import") (part "R-US_0204/7"))
    )
    (comp (ref "R31")
      (value "2R5")
      (footprint "eagle-import:0204_7")
      (fields (field (name "PARTNO") "660-MFS1/4DCT52R47R0"))
      (libsource (lib "eagle-import") (part "R-US_0204/7"))
    )
  )
  (nets
    (net (code "1") (name "3V3_PERIPHERAL") (class "Default")
      (node (ref "JP1") (pin "6") (pinfunction "6_6") (pintype "passive"))
      (node (ref "JP2") (pin "1") (pinfunction "1_1") (pintype "passive"))
      (node (ref "JP4") (pin "1") (pinfunction "1_1") (pintype "passive"))
      (node (ref "JP5") (pin "1") (pinfunction "1_1") (pintype "passive"))
      (node (ref "Q15") (pin "2") (pinfunction "C_2") (pintype "bidirectional"))
      (node (ref "QWIIC1") (pin "2") (pinfunction "V+_2") (pintype "passive"))
      (node (ref "R12") (pin "2") (pinfunction "2_2") (pintype "passive"))
      (node (ref "R29") (pin "2") (pinfunction "2_2") (pintype "passive"))
      (node (ref "R30") (pin "2") (pinfunction "2_2") (pintype "passive"))
    )
    (net (code "2") (name "3V3_PICO") (class "Default")
      (node (ref "C15") (pin "2") (pinfunction "2_2") (pintype "passive"))
      (node (ref "C16") (pin "2") (pinfunction "2_2") (pintype "passive"))
      (node (ref "C17") (pin "2") (pinfunction "2_2") (pintype "passive"))
      (node (ref "C18") (pin "2") (pinfunction "2_2") (pintype "passive"))
      (node (ref "IC13") (pin "6") (pinfunction "COL_6") (pintype "passive"))
      (node (ref "IC14") (pin "16") (pinfunction "VCC_16") (pintype "bidirectional"))
      (node (ref "IC15") (pin "16") (pinfunction "VCC_16") (pintype "bidirectional"))
      (node (ref "IC16") (pin "16") (pinfunction "VCC_16") (pintype "bidirectional"))
      (node (ref "IC17") (pin "16") (pinfunction "VCC_16") (pintype "bidirectional"))
      (node (ref "J10") (pin "1") (pinfunction "1_1") (pintype "bidirectional"))
      (node (ref "J9") (pin "4") (pinfunction "4_4") (pintype "bidirectional"))
      (node (ref "LED2") (pin "2") (pinfunction "COMMON_A_2") (pintype "bidirectional"))
      (node (ref "PICO1") (pin "3V3") (pinfunction "3V3_3V3") (pintype "bidirectional"))
      (node (ref "Q15") (pin "1") (pinfunction "E_1") (pintype "bidirectional"))
      (node (ref "R23") (pin "1") (pinfunction "1_1") (pintype "bidirectional"))
      (node (ref "R24") (pin "1") (pinfunction "1_1") (pintype "bidirectional"))
      (node (ref "R25") (pin "1") (pinfunction "1_1") (pintype "bidirectional"))
      (node (ref "R27") (pin "1") (pinfunction "1_1") (pintype "bidirectional"))
      (node (ref "R28") (pin "2") (pinfunction "2_2") (pintype "passive"))
      (node (ref "R34") (pin "2") (pinfunction "2_2") (pintype "passive"))
    )
    (net (code "3") (name "5V") (class "Default")
      (node (ref "C13") (pin "1") (pinfunction "1_1") (pintype "passive"))
      (node (ref "C14") (pin "1") (pinfunction "1_1") (pintype "passive"))
      (node (ref "IC11") (pin "14") (pinfunction "VCC_14") (pintype "bidirectional"))
      (node (ref "IC11") (pin "2") (pinfunction "1D_2") (pintype "bidirectional"))
      (node (ref "IC11") (pin "4") (pinfunction "1~{PRE}_4") (pintype "bidirectional"))
      (node (ref "IC12") (pin "2") (pinfunction "VDD_2") (pintype "power_in"))
      (node (ref "IC13") (pin "8") (pinfunction "COL_8") (pintype "passive"))
      (node (ref "J1") (pin "2") (pinfunction "2_2") (pintype "bidirectional"))
      (node (ref "J11") (pin "1") (pinfunction "1_1") (pintype "bidirectional"))
      (node (ref "J2") (pin "6") (pinfunction "6_6") (pintype "bidirectional"))
      (node (ref "J9") (pin "2") (pinfunction "2_2") (pintype "bidirectional"))
    )
    (net (code "4") (name "12V") (class "Default")
      (node (ref "C1") (pin "2") (pinfunction "2_2") (pintype "passive"))
      (node (ref "C10") (pin "2") (pinfunction "2_2") (pintype "passive"))
      (node (ref "C11") (pin "2") (pinfunction "2_2") (pintype "passive"))
      (node (ref "C12") (pin "2") (pinfunction "2_2") (pintype "passive"))
      (node (ref "C2") (pin "2") (pinfunction "2_2") (pintype "passive"))
      (node (ref "C3") (pin "2") (pinfunction "2_2") (pintype "passive"))
      (node (ref "C4") (pin "2") (pinfunction "2_2") (pintype "passive"))
      (node (ref "C5") (pin "2") (pinfunction "2_2") (pintype "passive"))
      (node (ref "C6") (pin "2") (pinfunction "2_2") (pintype "passive"))
      (node (ref "C7") (pin "2") (pinfunction "2_2") (pintype "passive"))
      (node (ref "C8") (pin "2") (pinfunction "2_2") (pintype "passive"))
      (node (ref "C9") (pin "2") (pinfunction "2_2") (pintype "passive"))
      (node (ref "IC1") (pin "1") (pinfunction "ENA_1") (pintype "input"))
      (node (ref "IC1") (pin "6") (pinfunction "VDD_6") (pintype "power_in"))
      (node (ref "IC1") (pin "8") (pinfunction "ENB_8") (pintype "input"))
      (node (ref "IC2") (pin "1") (pinfunction "ENA_1") (pintype "input"))
      (node (ref "IC2") (pin "6") (pinfunction "VDD_6") (pintype "power_in"))
      (node (ref "IC2") (pin "8") (pinfunction "ENB_8") (pintype "input"))
      (node (ref "IC3") (pin "1") (pinfunction "ENA_1") (pintype "input"))
      (node (ref "IC3") (pin "6") (pinfunction "VDD_6") (pintype "power_in"))
      (node (ref "IC3") (pin "8") (pinfunction "ENB_8") (pintype "input"))
      (node (ref "IC4") (pin "1") (pinfunction "ENA_1") (pintype "input"))
      (node (ref "IC4") (pin "6") (pinfunction "VDD_6") (pintype "power_in"))
      (node (ref "IC4") (pin "8") (pinfunction "ENB_8") (pintype "input"))
      (node (ref "IC5") (pin "1") (pinfunction "ENA_1") (pintype "input"))
      (node (ref "IC5") (pin "6") (pinfunction "VDD_6") (pintype "power_in"))
      (node (ref "IC5") (pin "8") (pinfunction "ENB_8") (pintype "input"))
      (node (ref "IC6") (pin "1") (pinfunction "ENA_1") (pintype "input"))
      (node (ref "IC6") (pin "6") (pinfunction "VDD_6") (pintype "power_in"))
      (node (ref "IC6") (pin "8") (pinfunction "ENB_8") (pintype "input"))
      (node (ref "J2") (pin "5") (pinfunction "5_5") (pintype "bidirectional"))
    )
    (net (code "5") (name "ACCEL_INTR") (class "Default")
      (node (ref "JP2") (pin "6") (pinfunction "6_6") (pintype "passive"))
      (node (ref "JP5") (pin "5") (pinfunction "5_5") (pintype "passive"))
      (node (ref "PICO1") (pin "GP22") (pinfunction "GP22_GP22") (pintype "bidirectional"))
    )
    (net (code "6") (name "ADC_INTR") (class "Default")
      (node (ref "JP4") (pin "6") (pinfunction "6_6") (pintype "passive"))
      (node (ref "PICO1") (pin "GP26_A0") (pinfunction "GP26_A0_GP26_A0") (pintype "bidirectional"))
    )
    (net (code "7") (name "BUTTON1") (class "Default")
      (node (ref "IC14") (pin "11") (pinfunction "A_11") (pintype "bidirectional"))
      (node (ref "J8") (pin "1") (pinfunction "1_1") (pintype "bidirectional"))
      (node (ref "R27") (pin "2") (pinfunction "2_2") (pintype "bidirectional"))
    )
    (net (code "8") (name "BUTTON2") (class "Default")
      (node (ref "IC14") (pin "12") (pinfunction "B_12") (pintype "bidirectional"))
      (node (ref "J8") (pin "2") (pinfunction "2_2") (pintype "bidirectional"))
      (node (ref "R27") (pin "3") (pinfunction "3_3") (pintype "bidirectional"))
    )
    (net (code "9") (name "BUTTON3") (class "Default")
      (node (ref "IC14") (pin "13") (pinfunction "C_13") (pintype "bidirectional"))
      (node (ref "J8") (pin "4") (pinfunction "4_4") (pintype "bidirectional"))
      (node (ref "R27") (pin "4") (pinfunction "4_4") (pintype "bidirectional"))
    )
    (net (code "10") (name "BUTTON4") (class "Default")
      (node (ref "IC14") (pin "14") (pinfunction "D_14") (pintype "bidirectional"))
      (node (ref "J8") (pin "5") (pinfunction "5_5") (pintype "bidirectional"))
      (node (ref "R27") (pin "5") (pinfunction "5_5") (pintype "bidirectional"))
    )
    (net (code "11") (name "BUTTON5") (class "Default")
      (node (ref "IC14") (pin "6") (pinfunction "H_6") (pintype "bidirectional"))
      (node (ref "J8") (pin "6") (pinfunction "6_6") (pintype "bidirectional"))
      (node (ref "R27") (pin "6") (pinfunction "6_6") (pintype "bidirectional"))
    )
    (net (code "12") (name "BUTTON6") (class "Default")
      (node (ref "IC14") (pin "5") (pinfunction "G_5") (pintype "bidirectional"))
      (node (ref "J8") (pin "7") (pinfunction "7_7") (pintype "bidirectional"))
      (node (ref "R27") (pin "7") (pinfunction "7_7") (pintype "bidirectional"))
    )
    (net (code "13") (name "BUTTON7") (class "Default")
      (node (ref "IC14") (pin "4") (pinfunction "F_4") (pintype "bidirectional"))
      (node (ref "J8") (pin "8") (pinfunction "8_8") (pintype "bidirectional"))
      (node (ref "R27") (pin "8") (pinfunction "8_8") (pintype "bidirectional"))
    )
    (net (code "14") (name "BUTTON8") (class "Default")
      (node (ref "IC14") (pin "3") (pinfunction "E_3") (pintype "bidirectional"))
      (node (ref "J8") (pin "9") (pinfunction "9_9") (pintype "bidirectional"))
      (node (ref "R27") (pin "9") (pinfunction "9_9") (pintype "bidirectional"))
    )
    (net (code "15") (name "BUTTON9") (class "Default")
      (node (ref "IC15") (pin "11") (pinfunction "A_11") (pintype "bidirectional"))
      (node (ref "J7") (pin "1") (pinfunction "1_1") (pintype "bidirectional"))
      (node (ref "R23") (pin "2") (pinfunction "2_2") (pintype "bidirectional"))
    )
    (net (code "16") (name "BUTTON10") (class "Default")
      (node (ref "IC15") (pin "12") (pinfunction "B_12") (pintype "bidirectional"))
      (node (ref "J7") (pin "2") (pinfunction "2_2") (pintype "bidirectional"))
      (node (ref "R23") (pin "3") (pinfunction "3_3") (pintype "bidirectional"))
    )
    (net (code "17") (name "BUTTON11") (class "Default")
      (node (ref "IC15") (pin "13") (pinfunction "C_13") (pintype "bidirectional"))
      (node (ref "J7") (pin "3") (pinfunction "3_3") (pintype "bidirectional"))
      (node (ref "R23") (pin "4") (pinfunction "4_4") (pintype "bidirectional"))
    )
    (net (code "18") (name "BUTTON12") (class "Default")
      (node (ref "IC15") (pin "14") (pinfunction "D_14") (pintype "bidirectional"))
      (node (ref "J7") (pin "5") (pinfunction "5_5") (pintype "bidirectional"))
      (node (ref "R23") (pin "5") (pinfunction "5_5") (pintype "bidirectional"))
    )
    (net (code "19") (name "BUTTON13") (class "Default")
      (node (ref "IC15") (pin "6") (pinfunction "H_6") (pintype "bidirectional"))
      (node (ref "J7") (pin "6") (pinfunction "6_6") (pintype "bidirectional"))
      (node (ref "R23") (pin "6") (pinfunction "6_6") (pintype "bidirectional"))
    )
    (net (code "20") (name "BUTTON14") (class "Default")
      (node (ref "IC15") (pin "5") (pinfunction "G_5") (pintype "bidirectional"))
      (node (ref "J7") (pin "7") (pinfunction "7_7") (pintype "bidirectional"))
      (node (ref "R23") (pin "7") (pinfunction "7_7") (pintype "bidirectional"))
    )
    (net (code "21") (name "BUTTON15") (class "Default")
      (node (ref "IC15") (pin "4") (pinfunction "F_4") (pintype "bidirectional"))
      (node (ref "J7") (pin "8") (pinfunction "8_8") (pintype "bidirectional"))
      (node (ref "R23") (pin "8") (pinfunction "8_8") (pintype "bidirectional"))
    )
    (net (code "22") (name "BUTTON16") (class "Default")
      (node (ref "IC15") (pin "3") (pinfunction "E_3") (pintype "bidirectional"))
      (node (ref "J7") (pin "9") (pinfunction "9_9") (pintype "bidirectional"))
      (node (ref "R23") (pin "9") (pinfunction "9_9") (pintype "bidirectional"))
    )
    (net (code "23") (name "BUTTON17") (class "Default")
      (node (ref "IC16") (pin "11") (pinfunction "A_11") (pintype "bidirectional"))
      (node (ref "J6") (pin "1") (pinfunction "1_1") (pintype "bidirectional"))
      (node (ref "R24") (pin "2") (pinfunction "2_2") (pintype "bidirectional"))
    )
    (net (code "24") (name "BUTTON18") (class "Default")
      (node (ref "IC16") (pin "12") (pinfunction "B_12") (pintype "bidirectional"))
      (node (ref "J6") (pin "2") (pinfunction "2_2") (pintype "bidirectional"))
      (node (ref "R24") (pin "3") (pinfunction "3_3") (pintype "bidirectional"))
    )
    (net (code "25") (name "BUTTON19") (class "Default")
      (node (ref "IC16") (pin "13") (pinfunction "C_13") (pintype "bidirectional"))
      (node (ref "J6") (pin "3") (pinfunction "3_3") (pintype "bidirectional"))
      (node (ref "R24") (pin "4") (pinfunction "4_4") (pintype "bidirectional"))
    )
    (net (code "26") (name "BUTTON20") (class "Default")
      (node (ref "IC16") (pin "14") (pinfunction "D_14") (pintype "bidirectional"))
      (node (ref "J6") (pin "4") (pinfunction "4_4") (pintype "bidirectional"))
      (node (ref "R24") (pin "5") (pinfunction "5_5") (pintype "bidirectional"))
    )
    (net (code "27") (name "BUTTON21") (class "Default")
      (node (ref "IC16") (pin "6") (pinfunction "H_6") (pintype "bidirectional"))
      (node (ref "J6") (pin "6") (pinfunction "6_6") (pintype "bidirectional"))
      (node (ref "R24") (pin "6") (pinfunction "6_6") (pintype "bidirectional"))
    )
    (net (code "28") (name "BUTTON22") (class "Default")
      (node (ref "IC16") (pin "5") (pinfunction "G_5") (pintype "bidirectional"))
      (node (ref "J6") (pin "7") (pinfunction "7_7") (pintype "bidirectional"))
      (node (ref "R24") (pin "7") (pinfunction "7_7") (pintype "bidirectional"))
    )
    (net (code "29") (name "BUTTON23") (class "Default")
      (node (ref "IC16") (pin "4") (pinfunction "F_4") (pintype "bidirectional"))
      (node (ref "J6") (pin "8") (pinfunction "8_8") (pintype "bidirectional"))
      (node (ref "R24") (pin "8") (pinfunction "8_8") (pintype "bidirectional"))
    )
    (net (code "30") (name "BUTTON24") (class "Default")
      (node (ref "IC16") (pin "3") (pinfunction "E_3") (pintype "bidirectional"))
      (node (ref "J6") (pin "9") (pinfunction "9_9") (pintype "bidirectional"))
      (node (ref "R24") (pin "9") (pinfunction "9_9") (pintype "bidirectional"))
    )
    (net (code "31") (name "BUTTON25") (class "Default")
      (node (ref "IC17") (pin "11") (pinfunction "A_11") (pintype "bidirectional"))
      (node (ref "J5") (pin "1") (pinfunction "1_1") (pintype "bidirectional"))
      (node (ref "R25") (pin "2") (pinfunction "2_2") (pintype "bidirectional"))
    )
    (net (code "32") (name "BUTTON26") (class "Default")
      (node (ref "IC17") (pin "12") (pinfunction "B_12") (pintype "bidirectional"))
      (node (ref "J5") (pin "2") (pinfunction "2_2") (pintype "bidirectional"))
      (node (ref "R25") (pin "3") (pinfunction "3_3") (pintype "bidirectional"))
    )
    (net (code "33") (name "BUTTON27") (class "Default")
      (node (ref "IC17") (pin "13") (pinfunction "C_13") (pintype "bidirectional"))
      (node (ref "J5") (pin "3") (pinfunction "3_3") (pintype "bidirectional"))
      (node (ref "R25") (pin "4") (pinfunction "4_4") (pintype "bidirectional"))
    )
    (net (code "34") (name "BUTTON28") (class "Default")
      (node (ref "IC17") (pin "14") (pinfunction "D_14") (pintype "bidirectional"))
      (node (ref "J5") (pin "4") (pinfunction "4_4") (pintype "bidirectional"))
      (node (ref "R25") (pin "5") (pinfunction "5_5") (pintype "bidirectional"))
    )
    (net (code "35") (name "BUTTON29") (class "Default")
      (node (ref "IC17") (pin "6") (pinfunction "H_6") (pintype "bidirectional"))
      (node (ref "J5") (pin "5") (pinfunction "5_5") (pintype "bidirectional"))
      (node (ref "R25") (pin "6") (pinfunction "6_6") (pintype "bidirectional"))
    )
    (net (code "36") (name "BUTTON30") (class "Default")
      (node (ref "IC17") (pin "5") (pinfunction "G_5") (pintype "bidirectional"))
      (node (ref "J5") (pin "7") (pinfunction "7_7") (pintype "bidirectional"))
      (node (ref "R25") (pin "7") (pinfunction "7_7") (pintype "bidirectional"))
    )
    (net (code "37") (name "BUTTON31") (class "Default")
      (node (ref "IC17") (pin "4") (pinfunction "F_4") (pintype "bidirectional"))
      (node (ref "J5") (pin "8") (pinfunction "8_8") (pintype "bidirectional"))
      (node (ref "R25") (pin "8") (pinfunction "8_8") (pintype "bidirectional"))
    )
    (net (code "38") (name "BUTTON32") (class "Default")
      (node (ref "IC17") (pin "3") (pinfunction "E_3") (pintype "bidirectional"))
      (node (ref "J5") (pin "9") (pinfunction "9_9") (pintype "bidirectional"))
      (node (ref "R25") (pin "9") (pinfunction "9_9") (pintype "bidirectional"))
    )
    (net (code "39") (name "BUTTON_CLK") (class "Default")
      (node (ref "IC14") (pin "2") (pinfunction "CLK_2") (pintype "bidirectional"))
      (node (ref "IC15") (pin "2") (pinfunction "CLK_2") (pintype "bidirectional"))
      (node (ref "IC16") (pin "2") (pinfunction "CLK_2") (pintype "bidirectional"))
      (node (ref "IC17") (pin "2") (pinfunction "CLK_2") (pintype "bidirectional"))
      (node (ref "PICO1") (pin "GP19") (pinfunction "GP19_GP19") (pintype "bidirectional"))
    )
    (net (code "40") (name "BUTTON_DATA") (class "Default")
      (node (ref "IC14") (pin "9") (pinfunction "QH_9") (pintype "bidirectional"))
      (node (ref "PICO1") (pin "GP18") (pinfunction "GP18_GP18") (pintype "bidirectional"))
    )
    (net (code "41") (name "BUTTON_SHLD") (class "Default")
      (node (ref "IC14") (pin "1") (pinfunction "SH/~{LD}_1") (pintype "bidirectional"))
      (node (ref "IC15") (pin "1") (pinfunction "SH/~{LD}_1") (pintype "bidirectional"))
      (node (ref "IC16") (pin "1") (pinfunction "SH/~{LD}_1") (pintype "bidirectional"))
      (node (ref "IC17") (pin "1") (pinfunction "SH/~{LD}_1") (pintype "bidirectional"))
      (node (ref "PICO1") (pin "GP20") (pinfunction "GP20_GP20") (pintype "bidirectional"))
    )
    (net (code "42") (name "FLASHCTL1") (class "Default")
      (node (ref "IC7") (pin "1") (pinfunction "I1_1") (pintype "input"))
      (node (ref "IC7") (pin "2") (pinfunction "I2_2") (pintype "input"))
      (node (ref "PICO2") (pin "GP3") (pinfunction "GP3_GP3") (pintype "bidirectional"))
    )
    (net (code "43") (name "FLASHCTL2") (class "Default")
      (node (ref "IC7") (pin "3") (pinfunction "I3_3") (pintype "input"))
      (node (ref "IC7") (pin "4") (pinfunction "I4_4") (pintype "input"))
      (node (ref "PICO2") (pin "GP2") (pinfunction "GP2_GP2") (pintype "bidirectional"))
    )
    (net (code "44") (name "FLASHCTL3") (class "Default")
      (node (ref "IC7") (pin "5") (pinfunction "I5_5") (pintype "input"))
      (node (ref "IC7") (pin "6") (pinfunction "I6_6") (pintype "input"))
      (node (ref "PICO2") (pin "GP1") (pinfunction "GP1_GP1") (pintype "bidirectional"))
    )
    (net (code "45") (name "FLASHCTL4") (class "Default")
      (node (ref "IC7") (pin "7") (pinfunction "I7_7") (pintype "input"))
      (node (ref "IC7") (pin "8") (pinfunction "I8_8") (pintype "input"))
      (node (ref "PICO2") (pin "GP0") (pinfunction "GP0_GP0") (pintype "bidirectional"))
    )
    (net (code "46") (name "FLASHCTL5") (class "Default")
      (node (ref "IC8") (pin "1") (pinfunction "I1_1") (pintype "input"))
      (node (ref "IC8") (pin "2") (pinfunction "I2_2") (pintype "input"))
      (node (ref "PICO2") (pin "GP4") (pinfunction "GP4_GP4") (pintype "bidirectional"))
    )
    (net (code "47") (name "FLASHCTL6") (class "Default")
      (node (ref "IC8") (pin "3") (pinfunction "I3_3") (pintype "input"))
      (node (ref "IC8") (pin "4") (pinfunction "I4_4") (pintype "input"))
      (node (ref "PICO2") (pin "GP5") (pinfunction "GP5_GP5") (pintype "bidirectional"))
    )
    (net (code "48") (name "FLASHCTL7") (class "Default")
      (node (ref "IC8") (pin "5") (pinfunction "I5_5") (pintype "input"))
      (node (ref "IC8") (pin "6") (pinfunction "I6_6") (pintype "input"))
      (node (ref "PICO2") (pin "GP6") (pinfunction "GP6_GP6") (pintype "bidirectional"))
    )
    (net (code "49") (name "FLASHCTL8") (class "Default")
      (node (ref "IC8") (pin "7") (pinfunction "I7_7") (pintype "input"))
      (node (ref "IC8") (pin "8") (pinfunction "I8_8") (pintype "input"))
      (node (ref "PICO2") (pin "GP7") (pinfunction "GP7_GP7") (pintype "bidirectional"))
    )
    (net (code "50") (name "FLASHCTL9") (class "Default")
      (node (ref "IC10") (pin "7") (pinfunction "I7_7") (pintype "input"))
      (node (ref "IC10") (pin "8") (pinfunction "I8_8") (pintype "input"))
      (node (ref "PICO2") (pin "GP8") (pinfunction "GP8_GP8") (pintype "bidirectional"))
    )
    (net (code "51") (name "FLASHCTL10") (class "Default")
      (node (ref "IC10") (pin "5") (pinfunction "I5_5") (pintype "input"))
      (node (ref "IC10") (pin "6") (pinfunction "I6_6") (pintype "input"))
      (node (ref "PICO2") (pin "GP9") (pinfunction "GP9_GP9") (pintype "bidirectional"))
    )
    (net (code "52") (name "FLASHCTL11") (class "Default")
      (node (ref "IC10") (pin "3") (pinfunction "I3_3") (pintype "input"))
      (node (ref "IC10") (pin "4") (pinfunction "I4_4") (pintype "input"))
      (node (ref "PICO2") (pin "GP10") (pinfunction "GP10_GP10") (pintype "bidirectional"))
    )
    (net (code "53") (name "FLASHCTL12") (class "Default")
      (node (ref "IC10") (pin "1") (pinfunction "I1_1") (pintype "input"))
      (node (ref "IC10") (pin "2") (pinfunction "I2_2") (pintype "input"))
      (node (ref "PICO2") (pin "GP11") (pinfunction "GP11_GP11") (pintype "bidirectional"))
    )
    (net (code "54") (name "FLASHCTL13") (class "Default")
      (node (ref "IC9") (pin "5") (pinfunction "I5_5") (pintype "input"))
      (node (ref "IC9") (pin "6") (pinfunction "I6_6") (pintype "input"))
      (node (ref "PICO2") (pin "GP14") (pinfunction "GP14_GP14") (pintype "bidirectional"))
    )
    (net (code "55") (name "FLASHCTL14") (class "Default")
      (node (ref "IC9") (pin "3") (pinfunction "I3_3") (pintype "input"))
      (node (ref "IC9") (pin "4") (pinfunction "I4_4") (pintype "input"))
      (node (ref "PICO2") (pin "GP13") (pinfunction "GP13_GP13") (pintype "bidirectional"))
    )
    (net (code "56") (name "FLASHCTL15") (class "Default")
      (node (ref "IC9") (pin "1") (pinfunction "I1_1") (pintype "input"))
      (node (ref "IC9") (pin "2") (pinfunction "I2_2") (pintype "input"))
      (node (ref "PICO2") (pin "GP12") (pinfunction "GP12_GP12") (pintype "bidirectional"))
    )
    (net (code "57") (name "FLASHCTL16") (class "Default")
      (node (ref "IC9") (pin "7") (pinfunction "I7_7") (pintype "input"))
      (node (ref "IC9") (pin "8") (pinfunction "I8_8") (pintype "input"))
      (node (ref "PICO2") (pin "GP15") (pinfunction "GP15_GP15") (pintype "bidirectional"))
    )
    (net (code "58") (name "FLASHER1") (class "Default")
      (node (ref "IC7") (pin "17") (pinfunction "O2_17") (pintype "open_collector"))
      (node (ref "IC7") (pin "18") (pinfunction "O1_18") (pintype "open_collector"))
      (node (ref "J1") (pin "15") (pinfunction "15_15") (pintype "bidirectional"))
    )
    (net (code "59") (name "FLASHER2") (class "Default")
      (node (ref "IC7") (pin "15") (pinfunction "O4_15") (pintype "open_collector"))
      (node (ref "IC7") (pin "16") (pinfunction "O3_16") (pintype "open_collector"))
      (node (ref "J1") (pin "13") (pinfunction "13_13") (pintype "bidirectional"))
    )
    (net (code "60") (name "FLASHER3") (class "Default")
      (node (ref "IC7") (pin "13") (pinfunction "O6_13") (pintype "open_collector"))
      (node (ref "IC7") (pin "14") (pinfunction "O5_14") (pintype "open_collector"))
      (node (ref "J1") (pin "11") (pinfunction "11_11") (pintype "bidirectional"))
    )
    (net (code "61") (name "FLASHER4") (class "Default")
      (node (ref "IC7") (pin "11") (pinfunction "O8_11") (pintype "open_collector"))
      (node (ref "IC7") (pin "12") (pinfunction "O7_12") (pintype "open_collector"))
      (node (ref "J1") (pin "9") (pinfunction "9_9") (pintype "bidirectional"))
    )
    (net (code "62") (name "FLASHER5") (class "Default")
      (node (ref "IC8") (pin "17") (pinfunction "O2_17") (pintype "open_collector"))
      (node (ref "IC8") (pin "18") (pinfunction "O1_18") (pintype "open_collector"))
      (node (ref "J1") (pin "7") (pinfunction "7_7") (pintype "bidirectional"))
    )
    (net (code "63") (name "FLASHER6") (class "Default")
      (node (ref "IC8") (pin "15") (pinfunction "O4_15") (pintype "open_collector"))
      (node (ref "IC8") (pin "16") (pinfunction "O3_16") (pintype "open_collector"))
      (node (ref "J1") (pin "5") (pinfunction "5_5") (pintype "bidirectional"))
    )
    (net (code "64") (name "FLASHER7") (class "Default")
      (node (ref "IC8") (pin "13") (pinfunction "O6_13") (pintype "open_collector"))
      (node (ref "IC8") (pin "14") (pinfunction "O5_14") (pintype "open_collector"))
      (node (ref "J1") (pin "3") (pinfunction "3_3") (pintype "bidirectional"))
    )
    (net (code "65") (name "FLASHER8") (class "Default")
      (node (ref "IC8") (pin "11") (pinfunction "O8_11") (pintype "open_collector"))
      (node (ref "IC8") (pin "12") (pinfunction "O7_12") (pintype "open_collector"))
      (node (ref "J1") (pin "1") (pinfunction "1_1") (pintype "bidirectional"))
    )
    (net (code "66") (name "FLASHER9") (class "Default")
      (node (ref "IC10") (pin "11") (pinfunction "O8_11") (pintype "open_collector"))
      (node (ref "IC10") (pin "12") (pinfunction "O7_12") (pintype "open_collector"))
      (node (ref "J1") (pin "16") (pinfunction "16_16") (pintype "bidirectional"))
    )
    (net (code "67") (name "FLASHER10") (class "Default")
      (node (ref "IC10") (pin "13") (pinfunction "O6_13") (pintype "open_collector"))
      (node (ref "IC10") (pin "14") (pinfunction "O5_14") (pintype "open_collector"))
      (node (ref "J1") (pin "14") (pinfunction "14_14") (pintype "bidirectional"))
    )
    (net (code "68") (name "FLASHER11") (class "Default")
      (node (ref "IC10") (pin "15") (pinfunction "O4_15") (pintype "open_collector"))
      (node (ref "IC10") (pin "16") (pinfunction "O3_16") (pintype "open_collector"))
      (node (ref "J1") (pin "12") (pinfunction "12_12") (pintype "bidirectional"))
    )
    (net (code "69") (name "FLASHER12") (class "Default")
      (node (ref "IC10") (pin "17") (pinfunction "O2_17") (pintype "open_collector"))
      (node (ref "IC10") (pin "18") (pinfunction "O1_18") (pintype "open_collector"))
      (node (ref "J1") (pin "10") (pinfunction "10_10") (pintype "bidirectional"))
    )
    (net (code "70") (name "FLASHER13") (class "Default")
      (node (ref "IC9") (pin "13") (pinfunction "O6_13") (pintype "open_collector"))
      (node (ref "IC9") (pin "14") (pinfunction "O5_14") (pintype "open_collector"))
      (node (ref "J1") (pin "8") (pinfunction "8_8") (pintype "bidirectional"))
    )
    (net (code "71") (name "FLASHER14") (class "Default")
      (node (ref "IC9") (pin "15") (pinfunction "O4_15") (pintype "open_collector"))
      (node (ref "IC9") (pin "16") (pinfunction "O3_16") (pintype "open_collector"))
      (node (ref "J1") (pin "6") (pinfunction "6_6") (pintype "bidirectional"))
    )
    (net (code "72") (name "FLASHER15") (class "Default")
      (node (ref "IC9") (pin "17") (pinfunction "O2_17") (pintype "open_collector"))
      (node (ref "IC9") (pin "18") (pinfunction "O1_18") (pintype "open_collector"))
      (node (ref "J1") (pin "4") (pinfunction "4_4") (pintype "bidirectional"))
    )
    (net (code "73") (name "FLASHER16") (class "Default")
      (node (ref "IC9") (pin "11") (pinfunction "O8_11") (pintype "open_collector"))
      (node (ref "IC9") (pin "12") (pinfunction "O7_12") (pintype "open_collector"))
      (node (ref "J13") (pin "1") (pinfunction "1_1") (pintype "bidirectional"))
    )
    (net (code "74") (name "GND") (class "Default")
      (node (ref "C1") (pin "1") (pinfunction "1_1") (pintype "passive"))
      (node (ref "C10") (pin "1") (pinfunction "1_1") (pintype "passive"))
      (node (ref "C11") (pin "1") (pinfunction "1_1") (pintype "passive"))
      (node (ref "C12") (pin "1") (pinfunction "1_1") (pintype "passive"))
      (node (ref "C13") (pin "2") (pinfunction "2_2") (pintype "passive"))
      (node (ref "C14") (pin "2") (pinfunction "2_2") (pintype "passive"))
      (node (ref "C15") (pin "1") (pinfunction "1_1") (pintype "passive"))
      (node (ref "C16") (pin "1") (pinfunction "1_1") (pintype "passive"))
      (node (ref "C17") (pin "1") (pinfunction "1_1") (pintype "passive"))
      (node (ref "C18") (pin "1") (pinfunction "1_1") (pintype "passive"))
      (node (ref "C2") (pin "1") (pinfunction "1_1") (pintype "passive"))
      (node (ref "C3") (pin "1") (pinfunction "1_1") (pintype "passive"))
      (node (ref "C4") (pin "1") (pinfunction "1_1") (pintype "passive"))
      (node (ref "C5") (pin "1") (pinfunction "1_1") (pintype "passive"))
      (node (ref "C6") (pin "1") (pinfunction "1_1") (pintype "passive"))
      (node (ref "C7") (pin "1") (pinfunction "1_1") (pintype "passive"))
      (node (ref "C8") (pin "1") (pinfunction "1_1") (pintype "passive"))
      (node (ref "C9") (pin "1") (pinfunction "1_1") (pintype "passive"))
      (node (ref "D4") (pin "C") (pinfunction "C_C") (pintype "passive"))
      (node (ref "IC1") (pin "3") (pinfunction "GND_3") (pintype "power_in"))
      (node (ref "IC10") (pin "9") (pinfunction "GND_9") (pintype "power_in"))
      (node (ref "IC11") (pin "7") (pinfunction "GND_7") (pintype "bidirectional"))
      (node (ref "IC12") (pin "3") (pinfunction "GND_3") (pintype "power_in"))
      (node (ref "IC14") (pin "15") (pinfunction "CLK_INH_15") (pintype "bidirectional"))
      (node (ref "IC14") (pin "8") (pinfunction "GND_8") (pintype "bidirectional"))
      (node (ref "IC15") (pin "15") (pinfunction "CLK_INH_15") (pintype "bidirectional"))
      (node (ref "IC15") (pin "8") (pinfunction "GND_8") (pintype "bidirectional"))
      (node (ref "IC16") (pin "15") (pinfunction "CLK_INH_15") (pintype "bidirectional"))
      (node (ref "IC16") (pin "8") (pinfunction "GND_8") (pintype "bidirectional"))
      (node (ref "IC17") (pin "15") (pinfunction "CLK_INH_15") (pintype "bidirectional"))
      (node (ref "IC17") (pin "8") (pinfunction "GND_8") (pintype "bidirectional"))
      (node (ref "IC2") (pin "3") (pinfunction "GND_3") (pintype "power_in"))
      (node (ref "IC3") (pin "3") (pinfunction "GND_3") (pintype "power_in"))
      (node (ref "IC4") (pin "3") (pinfunction "GND_3") (pintype "power_in"))
      (node (ref "IC5") (pin "3") (pinfunction "GND_3") (pintype "power_in"))
      (node (ref "IC6") (pin "3") (pinfunction "GND_3") (pintype "power_in"))
      (node (ref "IC7") (pin "9") (pinfunction "GND_9") (pintype "power_in"))
      (node (ref "IC8") (pin "9") (pinfunction "GND_9") (pintype "power_in"))
      (node (ref "IC9") (pin "9") (pinfunction "GND_9") (pintype "power_in"))
      (node (ref "J10") (pin "2") (pinfunction "2_2") (pintype "bidirectional"))
      (node (ref "J10") (pin "4") (pinfunction "4_4") (pintype "bidirectional"))
      (node (ref "J12") (pin "2") (pinfunction "2_2") (pintype "passive"))
      (node (ref "J13") (pin "2") (pinfunction "2_2") (pintype "bidirectional"))
      (node (ref "J14") (pin "2") (pinfunction "2_2") (pintype "bidirectional"))
      (node (ref "J14") (pin "4") (pinfunction "4_4") (pintype "bidirectional"))
      (node (ref "J14") (pin "6") (pinfunction "6_6") (pintype "bidirectional"))
      (node (ref "J14") (pin "8") (pinfunction "8_8") (pintype "bidirectional"))
      (node (ref "J2") (pin "1") (pinfunction "1_1") (pintype "bidirectional"))
      (node (ref "J2") (pin "2") (pinfunction "2_2") (pintype "bidirectional"))
      (node (ref "J2") (pin "3") (pinfunction "3_3") (pintype "bidirectional"))
      (node (ref "J2") (pin "4") (pinfunction "4_4") (pintype "bidirectional"))
      (node (ref "J5") (pin "10") (pinfunction "10_10") (pintype "bidirectional"))
      (node (ref "J6") (pin "10") (pinfunction "10_10") (pintype "bidirectional"))
      (node (ref "J7") (pin "10") (pinfunction "10_10") (pintype "bidirectional"))
      (node (ref "J8") (pin "10") (pinfunction "10_10") (pintype "bidirectional"))
      (node (ref "J9") (pin "3") (pinfunction "3_3") (pintype "bidirectional"))
      (node (ref "JP2") (pin "3") (pinfunction "3_3") (pintype "passive"))
      (node (ref "JP4") (pin "2") (pinfunction "2_2") (pintype "passive"))
      (node (ref "JP4") (pin "5") (pinfunction "5_5") (pintype "passive"))
      (node (ref "JP5") (pin "2") (pinfunction "2_2") (pintype "passive"))
      (node (ref "PICO1") (pin "AGND") (pinfunction "AGND_AGND") (pintype "bidirectional"))
      (node (ref "PICO1") (pin "GND@1") (pinfunction "GND_GND@1") (pintype "bidirectional"))
      (node (ref "PICO1") (pin "GND@2") (pinfunction "GND_GND@2") (pintype "bidirectional"))
      (node (ref "PICO1") (pin "GND@3") (pinfunction "GND_GND@3") (pintype "bidirectional"))
      (node (ref "PICO1") (pin "GND@4") (pinfunction "GND_GND@4") (pintype "bidirectional"))
      (node (ref "PICO1") (pin "GND@6") (pinfunction "GND_GND@6") (pintype "bidirectional"))
      (node (ref "PICO1") (pin "GND@7") (pinfunction "GND_GND@7") (pintype "bidirectional"))
      (node (ref "PICO1") (pin "GND@8") (pinfunction "GND_GND@8") (pintype "bidirectional"))
      (node (ref "PICO2") (pin "GND@1") (pinfunction "GND_GND@1") (pintype "bidirectional"))
      (node (ref "PICO2") (pin "GND@2") (pinfunction "GND_GND@2") (pintype "bidirectional"))
      (node (ref "PICO2") (pin "GND@3") (pinfunction "GND_GND@3") (pintype "bidirectional"))
      (node (ref "PICO2") (pin "GND@4") (pinfunction "GND_GND@4") (pintype "bidirectional"))
      (node (ref "PICO2") (pin "GND@6") (pinfunction "GND_GND@6") (pintype "bidirectional"))
      (node (ref "PICO2") (pin "GND@7") (pinfunction "GND_GND@7") (pintype "bidirectional"))
      (node (ref "PICO2") (pin "GND@8") (pinfunction "GND_GND@8") (pintype "bidirectional"))
      (node (ref "Q1") (pin "3") (pinfunction "S_3") (pintype "passive"))
      (node (ref "Q10") (pin "3") (pinfunction "S_3") (pintype "passive"))
      (node (ref "Q11") (pin "3") (pinfunction "S_3") (pintype "passive"))
      (node (ref "Q12") (pin "3") (pinfunction "S_3") (pintype "passive"))
      (node (ref "Q16") (pin "1") (pinfunction "E_1") (pintype "bidirectional"))
      (node (ref "Q2") (pin "3") (pinfunction "S_3") (pintype "passive"))
      (node (ref "Q3") (pin "3") (pinfunction "S_3") (pintype "passive"))
      (node (ref "Q4") (pin "3") (pinfunction "S_3") (pintype "passive"))
      (node (ref "Q5") (pin "3") (pinfunction "S_3") (pintype "passive"))
      (node (ref "Q6") (pin "3") (pinfunction "S_3") (pintype "passive"))
      (node (ref "Q7") (pin "3") (pinfunction "S_3") (pintype "passive"))
      (node (ref "Q8") (pin "3") (pinfunction "S_3") (pintype "passive"))
      (node (ref "Q9") (pin "3") (pinfunction "S_3") (pintype "passive"))
      (node (ref "QWIIC1") (pin "1") (pinfunction "GND_1") (pintype "passive"))
      (node (ref "QWIIC1") (pin "MT1") (pinfunction "MT_MT1") (pintype "bidirectional"))
      (node (ref "QWIIC1") (pin "MT2") (pinfunction "MT_MT2") (pintype "bidirectional"))
      (node (ref "R13") (pin "1") (pinfunction "1_1") (pintype "passive"))
      (node (ref "R18") (pin "1") (pinfunction "1_1") (pintype "passive"))
      (node (ref "R20") (pin "2") (pinfunction "2_2") (pintype "passive"))
      (node (ref "R21") (pin "1") (pinfunction "1_1") (pintype "passive"))
      (node (ref "R22") (pin "1") (pinfunction "1_1") (pintype "passive"))
      (node (ref "R31") (pin "1") (pinfunction "1_1") (pintype "passive"))
      (node (ref "S1") (pin "1") (pinfunction "S_1") (pintype "passive"))
      (node (ref "S1") (pin "2") (pinfunction "S1_2") (pintype "passive"))
      (node (ref "S2") (pin "1") (pinfunction "S_1") (pintype "passive"))
      (node (ref "S2") (pin "2") (pinfunction "S1_2") (pintype "passive"))
    )
    (net (code "75") (name "IR_IN") (class "Default")
      (node (ref "J10") (pin "3") (pinfunction "3_3") (pintype "bidirectional"))
      (node (ref "PICO1") (pin "GP4") (pinfunction "GP4_GP4") (pintype "bidirectional"))
    )
    (net (code "76") (name "IR_LED_CATHODE") (class "Default")
      (node (ref "J11") (pin "2") (pinfunction "2_2") (pintype "bidirectional"))
      (node (ref "Q13") (pin "1") (pinfunction "C_1") (pintype "bidirectional"))
    )
    (net (code "77") (name "IR_OUT") (class "Default")
      (node (ref "PICO1") (pin "GP0") (pinfunction "GP0_GP0") (pintype "bidirectional"))
      (node (ref "R19") (pin "1") (pinfunction "1_1") (pintype "passive"))
    )
    (net (code "78") (name "LED_B") (class "Default")
      (node (ref "PICO1") (pin "GP2") (pinfunction "GP2_GP2") (pintype "bidirectional"))
      (node (ref "R10") (pin "1") (pinfunction "1_1") (pintype "passive"))
    )
    (net (code "79") (name "LED_G") (class "Default")
      (node (ref "PICO1") (pin "GP1") (pinfunction "GP1_GP1") (pintype "bidirectional"))
      (node (ref "R11") (pin "1") (pinfunction "1_1") (pintype "passive"))
    )
    (net (code "80") (name "LED_R") (class "Default")
      (node (ref "PICO1") (pin "GP3") (pinfunction "GP3_GP3") (pintype "bidirectional"))
      (node (ref "R9") (pin "1") (pinfunction "1_1") (pintype "passive"))
    )
    (net (code "81") (name "Net-(D1-K)") (class "Default")
      (node (ref "D1") (pin "1") (pinfunction "K_1") (pintype "bidirectional"))
      (node (ref "PICO2") (pin "VSYS") (pinfunction "VSYS_VSYS") (pintype "bidirectional"))
    )
    (net (code "82") (name "Net-(D3-PadC)") (class "Default")
      (node (ref "D3") (pin "C") (pinfunction "C_C") (pintype "passive"))
      (node (ref "D4") (pin "A") (pinfunction "A_A") (pintype "passive"))
    )
    (net (code "83") (name "Net-(IC1-OUTA)") (class "Default")
      (node (ref "IC1") (pin "7") (pinfunction "OUTA_7") (pintype "output"))
      (node (ref "R1") (pin "1") (pinfunction "1_1") (pintype "passive"))
    )
    (net (code "84") (name "Net-(IC1-OUTB)") (class "Default")
      (node (ref "IC1") (pin "5") (pinfunction "OUTB_5") (pintype "output"))
      (node (ref "R2") (pin "1") (pinfunction "1_1") (pintype "passive"))
    )
    (net (code "85") (name "Net-(IC2-OUTA)") (class "Default")
      (node (ref "IC2") (pin "7") (pinfunction "OUTA_7") (pintype "output"))
      (node (ref "R3") (pin "1") (pinfunction "1_1") (pintype "passive"))
    )
    (net (code "86") (name "Net-(IC2-OUTB)") (class "Default")
      (node (ref "IC2") (pin "5") (pinfunction "OUTB_5") (pintype "output"))
      (node (ref "R4") (pin "1") (pinfunction "1_1") (pintype "passive"))
    )
    (net (code "87") (name "Net-(IC3-OUTA)") (class "Default")
      (node (ref "IC3") (pin "7") (pinfunction "OUTA_7") (pintype "output"))
      (node (ref "R5") (pin "1") (pinfunction "1_1") (pintype "passive"))
    )
    (net (code "88") (name "Net-(IC3-OUTB)") (class "Default")
      (node (ref "IC3") (pin "5") (pinfunction "OUTB_5") (pintype "output"))
      (node (ref "R6") (pin "1") (pinfunction "1_1") (pintype "passive"))
    )
    (net (code "89") (name "Net-(IC4-OUTA)") (class "Default")
      (node (ref "IC4") (pin "7") (pinfunction "OUTA_7") (pintype "output"))
      (node (ref "R7") (pin "1") (pinfunction "1_1") (pintype "passive"))
    )
    (net (code "90") (name "Net-(IC4-OUTB)") (class "Default")
      (node (ref "IC4") (pin "5") (pinfunction "OUTB_5") (pintype "output"))
      (node (ref "R8") (pin "1") (pinfunction "1_1") (pintype "passive"))
    )
    (net (code "91") (name "Net-(IC5-OUTA)") (class "Default")
      (node (ref "IC5") (pin "7") (pinfunction "OUTA_7") (pintype "output"))
      (node (ref "R14") (pin "1") (pinfunction "1_1") (pintype "passive"))
    )
    (net (code "92") (name "Net-(IC5-OUTB)") (class "Default")
      (node (ref "IC5") (pin "5") (pinfunction "OUTB_5") (pintype "output"))
      (node (ref "R15") (pin "1") (pinfunction "1_1") (pintype "passive"))
    )
    (net (code "93") (name "Net-(IC6-OUTA)") (class "Default")
      (node (ref "IC6") (pin "7") (pinfunction "OUTA_7") (pintype "output"))
      (node (ref "R16") (pin "1") (pinfunction "1_1") (pintype "passive"))
    )
    (net (code "94") (name "Net-(IC6-OUTB)") (class "Default")
      (node (ref "IC6") (pin "5") (pinfunction "OUTB_5") (pintype "output"))
      (node (ref "R17") (pin "1") (pinfunction "1_1") (pintype "passive"))
    )
    (net (code "95") (name "Net-(IC11-1CLK)") (class "Default")
      (node (ref "IC11") (pin "3") (pinfunction "1CLK_3") (pintype "bidirectional"))
      (node (ref "IC13") (pin "7") (pinfunction "EMIT_7") (pintype "passive"))
      (node (ref "R20") (pin "1") (pinfunction "1_1") (pintype "passive"))
    )
    (net (code "96") (name "Net-(IC11-1Q)") (class "Default")
      (node (ref "IC11") (pin "5") (pinfunction "1Q_5") (pintype "bidirectional"))
      (node (ref "IC13") (pin "3") (pinfunction "A_3") (pintype "passive"))
    )
    (net (code "97") (name "Net-(IC11-~{1CLR})") (class "Default")
      (node (ref "IC11") (pin "1") (pinfunction "~{1CLR}_1") (pintype "bidirectional"))
      (node (ref "IC12") (pin "1") (pinfunction "OUT_1") (pintype "output"))
    )
    (net (code "98") (name "Net-(IC13A-C)") (class "Default")
      (node (ref "IC13") (pin "2") (pinfunction "C_2") (pintype "passive"))
      (node (ref "R18") (pin "2") (pinfunction "2_2") (pintype "passive"))
    )
    (net (code "99") (name "Net-(IC13B-C)") (class "Default")
      (node (ref "IC13") (pin "4") (pinfunction "C_4") (pintype "passive"))
      (node (ref "R21") (pin "2") (pinfunction "2_2") (pintype "passive"))
    )
    (net (code "100") (name "Net-(IC14-SER)") (class "Default")
      (node (ref "IC14") (pin "10") (pinfunction "SER_10") (pintype "bidirectional"))
      (node (ref "IC15") (pin "9") (pinfunction "QH_9") (pintype "bidirectional"))
    )
    (net (code "101") (name "Net-(IC15-SER)") (class "Default")
      (node (ref "IC15") (pin "10") (pinfunction "SER_10") (pintype "bidirectional"))
      (node (ref "IC16") (pin "9") (pinfunction "QH_9") (pintype "bidirectional"))
    )
    (net (code "102") (name "Net-(IC16-SER)") (class "Default")
      (node (ref "IC16") (pin "10") (pinfunction "SER_10") (pintype "bidirectional"))
      (node (ref "IC17") (pin "9") (pinfunction "QH_9") (pintype "bidirectional"))
    )
    (net (code "103") (name "Net-(JP3-Pad2)") (class "Default")
      (node (ref "JP3") (pin "2") (pinfunction "2_2") (pintype "passive"))
      (node (ref "R12") (pin "1") (pinfunction "1_1") (pintype "passive"))
      (node (ref "R13") (pin "2") (pinfunction "2_2") (pintype "passive"))
    )
    (net (code "104") (name "Net-(LED2-BLUE_K)") (class "Default")
      (node (ref "LED2") (pin "3") (pinfunction "BLUE_K_3") (pintype "bidirectional"))
      (node (ref "R10") (pin "2") (pinfunction "2_2") (pintype "passive"))
    )
    (net (code "105") (name "Net-(LED2-GREEN_K)") (class "Default")
      (node (ref "LED2") (pin "4") (pinfunction "GREEN_K_4") (pintype "bidirectional"))
      (node (ref "R11") (pin "2") (pinfunction "2_2") (pintype "passive"))
    )
    (net (code "106") (name "Net-(LED2-RED_K)") (class "Default")
      (node (ref "LED2") (pin "1") (pinfunction "RED_K_1") (pintype "bidirectional"))
      (node (ref "R9") (pin "2") (pinfunction "2_2") (pintype "passive"))
    )
    (net (code "107") (name "Net-(PICO2-Pad3V3)") (class "Default")
      (node (ref "PICO2") (pin "3V3") (pinfunction "3V3_3V3") (pintype "bidirectional"))
      (node (ref "R32") (pin "2") (pinfunction "2_2") (pintype "passive"))
    )
    (net (code "108") (name "Net-(Q1-G)") (class "Default")
      (node (ref "Q1") (pin "1") (pinfunction "G_1") (pintype "passive"))
      (node (ref "R1") (pin "2") (pinfunction "2_2") (pintype "passive"))
    )
    (net (code "109") (name "Net-(Q2-G)") (class "Default")
      (node (ref "Q2") (pin "1") (pinfunction "G_1") (pintype "passive"))
      (node (ref "R2") (pin "2") (pinfunction "2_2") (pintype "passive"))
    )
    (net (code "110") (name "Net-(Q3-G)") (class "Default")
      (node (ref "Q3") (pin "1") (pinfunction "G_1") (pintype "passive"))
      (node (ref "R3") (pin "2") (pinfunction "2_2") (pintype "passive"))
    )
    (net (code "111") (name "Net-(Q4-G)") (class "Default")
      (node (ref "Q4") (pin "1") (pinfunction "G_1") (pintype "passive"))
      (node (ref "R4") (pin "2") (pinfunction "2_2") (pintype "passive"))
    )
    (net (code "112") (name "Net-(Q5-G)") (class "Default")
      (node (ref "Q5") (pin "1") (pinfunction "G_1") (pintype "passive"))
      (node (ref "R5") (pin "2") (pinfunction "2_2") (pintype "passive"))
    )
    (net (code "113") (name "Net-(Q6-G)") (class "Default")
      (node (ref "Q6") (pin "1") (pinfunction "G_1") (pintype "passive"))
      (node (ref "R6") (pin "2") (pinfunction "2_2") (pintype "passive"))
    )
    (net (code "114") (name "Net-(Q7-G)") (class "Default")
      (node (ref "Q7") (pin "1") (pinfunction "G_1") (pintype "passive"))
      (node (ref "R7") (pin "2") (pinfunction "2_2") (pintype "passive"))
    )
    (net (code "115") (name "Net-(Q8-G)") (class "Default")
      (node (ref "Q8") (pin "1") (pinfunction "G_1") (pintype "passive"))
      (node (ref "R8") (pin "2") (pinfunction "2_2") (pintype "passive"))
    )
    (net (code "116") (name "Net-(Q9-G)") (class "Default")
      (node (ref "Q9") (pin "1") (pinfunction "G_1") (pintype "passive"))
      (node (ref "R14") (pin "2") (pinfunction "2_2") (pintype "passive"))
    )
    (net (code "117") (name "Net-(Q10-G)") (class "Default")
      (node (ref "Q10") (pin "1") (pinfunction "G_1") (pintype "passive"))
      (node (ref "R15") (pin "2") (pinfunction "2_2") (pintype "passive"))
    )
    (net (code "118") (name "Net-(Q11-G)") (class "Default")
      (node (ref "Q11") (pin "1") (pinfunction "G_1") (pintype "passive"))
      (node (ref "R16") (pin "2") (pinfunction "2_2") (pintype "passive"))
    )
    (net (code "119") (name "Net-(Q12-G)") (class "Default")
      (node (ref "Q12") (pin "1") (pinfunction "G_1") (pintype "passive"))
      (node (ref "R17") (pin "2") (pinfunction "2_2") (pintype "passive"))
    )
    (net (code "120") (name "Net-(Q13-B)") (class "Default")
      (node (ref "D3") (pin "A") (pinfunction "A_A") (pintype "passive"))
      (node (ref "Q13") (pin "2") (pinfunction "B_2") (pintype "bidirectional"))
      (node (ref "R19") (pin "2") (pinfunction "2_2") (pintype "passive"))
    )
    (net (code "121") (name "Net-(Q13-E)") (class "Default")
      (node (ref "Q13") (pin "3") (pinfunction "E_3") (pintype "bidirectional"))
      (node (ref "R31") (pin "2") (pinfunction "2_2") (pintype "passive"))
    )
    (net (code "122") (name "Net-(Q15-B)") (class "Default")
      (node (ref "Q15") (pin "3") (pinfunction "B_3") (pintype "bidirectional"))
      (node (ref "R26") (pin "2") (pinfunction "2_2") (pintype "passive"))
    )
    (net (code "123") (name "Net-(Q16-B)") (class "Default")
      (node (ref "Q16") (pin "2") (pinfunction "B_2") (pintype "bidirectional"))
      (node (ref "R33") (pin "2") (pinfunction "2_2") (pintype "passive"))
    )
    (net (code "124") (name "Net-(Q16-C)") (class "Default")
      (node (ref "PICO2") (pin "RUN") (pinfunction "RUN_RUN") (pintype "bidirectional"))
      (node (ref "Q16") (pin "3") (pinfunction "C_3") (pintype "bidirectional"))
      (node (ref "R32") (pin "1") (pinfunction "1_1") (pintype "passive"))
      (node (ref "S2") (pin "3") (pinfunction "P_3") (pintype "passive"))
      (node (ref "S2") (pin "4") (pinfunction "P1_4") (pintype "passive"))
    )
    (net (code "125") (name "Net-(S1-P)") (class "Default")
      (node (ref "PICO1") (pin "RUN") (pinfunction "RUN_RUN") (pintype "bidirectional"))
      (node (ref "R34") (pin "1") (pinfunction "1_1") (pintype "passive"))
      (node (ref "S1") (pin "3") (pinfunction "P_3") (pintype "passive"))
      (node (ref "S1") (pin "4") (pinfunction "P1_4") (pintype "passive"))
    )
    (net (code "126") (name "OUT1") (class "Default")
      (node (ref "J4") (pin "1") (pinfunction "1_1") (pintype "bidirectional"))
      (node (ref "Q1") (pin "2") (pinfunction "D_2") (pintype "passive"))
    )
    (net (code "127") (name "OUT2") (class "Default")
      (node (ref "J4") (pin "3") (pinfunction "3_3") (pintype "bidirectional"))
      (node (ref "Q2") (pin "2") (pinfunction "D_2") (pintype "passive"))
    )
    (net (code "128") (name "OUT3") (class "Default")
      (node (ref "J4") (pin "4") (pinfunction "4_4") (pintype "bidirectional"))
      (node (ref "Q3") (pin "2") (pinfunction "D_2") (pintype "passive"))
    )
    (net (code "129") (name "OUT4") (class "Default")
      (node (ref "J4") (pin "5") (pinfunction "5_5") (pintype "bidirectional"))
      (node (ref "Q4") (pin "2") (pinfunction "D_2") (pintype "passive"))
    )
    (net (code "130") (name "OUT5") (class "Default")
      (node (ref "J4") (pin "6") (pinfunction "6_6") (pintype "bidirectional"))
      (node (ref "Q5") (pin "2") (pinfunction "D_2") (pintype "passive"))
    )
    (net (code "131") (name "OUT6") (class "Default")
      (node (ref "J4") (pin "7") (pinfunction "7_7") (pintype "bidirectional"))
      (node (ref "Q6") (pin "2") (pinfunction "D_2") (pintype "passive"))
    )
    (net (code "132") (name "OUT7") (class "Default")
      (node (ref "J4") (pin "8") (pinfunction "8_8") (pintype "bidirectional"))
      (node (ref "Q7") (pin "2") (pinfunction "D_2") (pintype "passive"))
    )
    (net (code "133") (name "OUT8") (class "Default")
      (node (ref "J4") (pin "9") (pinfunction "9_9") (pintype "bidirectional"))
      (node (ref "Q8") (pin "2") (pinfunction "D_2") (pintype "passive"))
    )
    (net (code "134") (name "OUT9") (class "Default")
      (node (ref "J3") (pin "1") (pinfunction "1_1") (pintype "bidirectional"))
      (node (ref "Q9") (pin "2") (pinfunction "D_2") (pintype "passive"))
    )
    (net (code "135") (name "OUT10") (class "Default")
      (node (ref "J3") (pin "3") (pinfunction "3_3") (pintype "bidirectional"))
      (node (ref "Q10") (pin "2") (pinfunction "D_2") (pintype "passive"))
    )
    (net (code "136") (name "OUT11") (class "Default")
      (node (ref "J3") (pin "4") (pinfunction "4_4") (pintype "bidirectional"))
      (node (ref "Q11") (pin "2") (pinfunction "D_2") (pintype "passive"))
    )
    (net (code "137") (name "OUT12") (class "Default")
      (node (ref "J3") (pin "5") (pinfunction "5_5") (pintype "bidirectional"))
      (node (ref "Q12") (pin "2") (pinfunction "D_2") (pintype "passive"))
    )
    (net (code "138") (name "OUTCTL1") (class "Default")
      (node (ref "IC1") (pin "2") (pinfunction "INA_2") (pintype "input"))
      (node (ref "PICO1") (pin "GP8") (pinfunction "GP8_GP8") (pintype "bidirectional"))
    )
    (net (code "139") (name "OUTCTL2") (class "Default")
      (node (ref "IC1") (pin "4") (pinfunction "INB_4") (pintype "input"))
      (node (ref "PICO1") (pin "GP9") (pinfunction "GP9_GP9") (pintype "bidirectional"))
    )
    (net (code "140") (name "OUTCTL3") (class "Default")
      (node (ref "IC2") (pin "2") (pinfunction "INA_2") (pintype "input"))
      (node (ref "PICO1") (pin "GP14") (pinfunction "GP14_GP14") (pintype "bidirectional"))
    )
    (net (code "141") (name "OUTCTL4") (class "Default")
      (node (ref "IC2") (pin "4") (pinfunction "INB_4") (pintype "input"))
      (node (ref "PICO1") (pin "GP15") (pinfunction "GP15_GP15") (pintype "bidirectional"))
    )
    (net (code "142") (name "OUTCTL5") (class "Default")
      (node (ref "IC3") (pin "2") (pinfunction "INA_2") (pintype "input"))
      (node (ref "PICO2") (pin "GP16") (pinfunction "GP16_GP16") (pintype "bidirectional"))
    )
    (net (code "143") (name "OUTCTL6") (class "Default")
      (node (ref "IC3") (pin "4") (pinfunction "INB_4") (pintype "input"))
      (node (ref "PICO2") (pin "GP17") (pinfunction "GP17_GP17") (pintype "bidirectional"))
    )
    (net (code "144") (name "OUTCTL7") (class "Default")
      (node (ref "IC4") (pin "2") (pinfunction "INA_2") (pintype "input"))
      (node (ref "PICO2") (pin "GP18") (pinfunction "GP18_GP18") (pintype "bidirectional"))
    )
    (net (code "145") (name "OUTCTL8") (class "Default")
      (node (ref "IC4") (pin "4") (pinfunction "INB_4") (pintype "input"))
      (node (ref "PICO2") (pin "GP19") (pinfunction "GP19_GP19") (pintype "bidirectional"))
    )
    (net (code "146") (name "OUTCTL9") (class "Default")
      (node (ref "IC5") (pin "2") (pinfunction "INA_2") (pintype "input"))
      (node (ref "PICO2") (pin "GP22") (pinfunction "GP22_GP22") (pintype "bidirectional"))
    )
    (net (code "147") (name "OUTCTL10") (class "Default")
      (node (ref "IC5") (pin "4") (pinfunction "INB_4") (pintype "input"))
      (node (ref "PICO2") (pin "GP21") (pinfunction "GP21_GP21") (pintype "bidirectional"))
    )
    (net (code "148") (name "OUTCTL11") (class "Default")
      (node (ref "IC6") (pin "2") (pinfunction "INA_2") (pintype "input"))
      (node (ref "PICO2") (pin "GP20") (pinfunction "GP20_GP20") (pintype "bidirectional"))
    )
    (net (code "149") (name "OUTCTL12") (class "Default")
      (node (ref "IC6") (pin "4") (pinfunction "INB_4") (pintype "input"))
      (node (ref "PICO2") (pin "GP28_A2") (pinfunction "GP28_A2_GP28_A2") (pintype "bidirectional"))
    )
    (net (code "150") (name "PLUNGER_ADC") (class "Default")
      (node (ref "J9") (pin "8") (pinfunction "8_8") (pintype "bidirectional"))
      (node (ref "JP3") (pin "5") (pinfunction "5_5") (pintype "passive"))
      (node (ref "PICO1") (pin "GP28_A2") (pinfunction "GP28_A2_GP28_A2") (pintype "bidirectional"))
    )
    (net (code "151") (name "PLUNGER_IRQ1_SCL") (class "Default")
      (node (ref "J9") (pin "6") (pinfunction "6_6") (pintype "bidirectional"))
      (node (ref "PICO1") (pin "GP13") (pinfunction "GP13_GP13") (pintype "bidirectional"))
    )
    (net (code "152") (name "PLUNGER_IRQ2") (class "Default")
      (node (ref "J9") (pin "5") (pinfunction "5_5") (pintype "bidirectional"))
      (node (ref "PICO1") (pin "GP27_A1") (pinfunction "GP27_A1_GP27_A1") (pintype "bidirectional"))
    )
    (net (code "153") (name "PLUNGER_SDA") (class "Default")
      (node (ref "J9") (pin "1") (pinfunction "1_1") (pintype "bidirectional"))
      (node (ref "PICO1") (pin "GP12") (pinfunction "GP12_GP12") (pintype "bidirectional"))
    )
    (net (code "154") (name "PSU2_STATUS_SENSE") (class "Default")
      (node (ref "IC13") (pin "5") (pinfunction "EMIT_5") (pintype "passive"))
      (node (ref "PICO1") (pin "GP11") (pinfunction "GP11_GP11") (pintype "bidirectional"))
      (node (ref "R22") (pin "2") (pinfunction "2_2") (pintype "passive"))
    )
    (net (code "155") (name "PSU2_STATUS_SET") (class "Default")
      (node (ref "IC13") (pin "1") (pinfunction "A_1") (pintype "passive"))
      (node (ref "PICO1") (pin "GP10") (pinfunction "GP10_GP10") (pintype "bidirectional"))
    )
    (net (code "156") (name "SCL") (class "Default")
      (node (ref "J14") (pin "3") (pinfunction "3_3") (pintype "bidirectional"))
      (node (ref "JP2") (pin "4") (pinfunction "4_4") (pintype "passive"))
      (node (ref "JP4") (pin "3") (pinfunction "3_3") (pintype "passive"))
      (node (ref "JP5") (pin "6") (pinfunction "6_6") (pintype "passive"))
      (node (ref "PICO1") (pin "GP7") (pinfunction "GP7_GP7") (pintype "bidirectional"))
      (node (ref "PICO2") (pin "GP27_A1") (pinfunction "GP27_A1_GP27_A1") (pintype "bidirectional"))
      (node (ref "QWIIC1") (pin "4") (pinfunction "SCL_4") (pintype "passive"))
      (node (ref "R30") (pin "1") (pinfunction "1_1") (pintype "passive"))
    )
    (net (code "157") (name "SDA") (class "Default")
      (node (ref "J14") (pin "5") (pinfunction "5_5") (pintype "bidirectional"))
      (node (ref "JP2") (pin "5") (pinfunction "5_5") (pintype "passive"))
      (node (ref "JP4") (pin "4") (pinfunction "4_4") (pintype "passive"))
      (node (ref "JP5") (pin "7") (pinfunction "7_7") (pintype "passive"))
      (node (ref "PICO1") (pin "GP6") (pinfunction "GP6_GP6") (pintype "bidirectional"))
      (node (ref "PICO2") (pin "GP26_A0") (pinfunction "GP26_A0_GP26_A0") (pintype "bidirectional"))
      (node (ref "QWIIC1") (pin "3") (pinfunction "SDA_3") (pintype "passive"))
      (node (ref "R29") (pin "1") (pinfunction "1_1") (pintype "passive"))
    )
    (net (code "158") (name "UART0_RX") (class "Default")
      (node (ref "J12") (pin "3") (pinfunction "3_3") (pintype "passive"))
      (node (ref "PICO1") (pin "GP17") (pinfunction "GP17_GP17") (pintype "bidirectional"))
    )
    (net (code "159") (name "UART0_TX") (class "Default")
      (node (ref "J12") (pin "1") (pinfunction "1_1") (pintype "passive"))
      (node (ref "PICO1") (pin "GP16") (pinfunction "GP16_GP16") (pintype "bidirectional"))
    )
    (net (code "160") (name "VBUS") (class "Default")
      (node (ref "D1") (pin "2") (pinfunction "A_2") (pintype "bidirectional"))
      (node (ref "J14") (pin "1") (pinfunction "1_1") (pintype "bidirectional"))
      (node (ref "PICO1") (pin "VBUS") (pinfunction "VBUS_VBUS") (pintype "bidirectional"))
    )
    (net (code "161") (name "unconnected-(IC7-CD+-Pad10)") (class "Default")
      (node (ref "IC7") (pin "10") (pinfunction "CD+_10") (pintype "passive"))
    )
    (net (code "162") (name "unconnected-(IC8-CD+-Pad10)") (class "Default")
      (node (ref "IC8") (pin "10") (pinfunction "CD+_10") (pintype "passive"))
    )
    (net (code "163") (name "unconnected-(IC9-CD+-Pad10)") (class "Default")
      (node (ref "IC9") (pin "10") (pinfunction "CD+_10") (pintype "passive"))
    )
    (net (code "164") (name "unconnected-(IC10-CD+-Pad10)") (class "Default")
      (node (ref "IC10") (pin "10") (pinfunction "CD+_10") (pintype "passive"))
    )
    (net (code "165") (name "unconnected-(IC11-1~{Q}-Pad6)") (class "Default")
      (node (ref "IC11") (pin "6") (pinfunction "1~{Q}_6") (pintype "bidirectional"))
    )
    (net (code "166") (name "unconnected-(IC11-2CLK-Pad11)") (class "Default")
      (node (ref "IC11") (pin "11") (pinfunction "2CLK_11") (pintype "bidirectional"))
    )
    (net (code "167") (name "unconnected-(IC11-2D-Pad12)") (class "Default")
      (node (ref "IC11") (pin "12") (pinfunction "2D_12") (pintype "bidirectional"))
    )
    (net (code "168") (name "unconnected-(IC11-2Q-Pad9)") (class "Default")
      (node (ref "IC11") (pin "9") (pinfunction "2Q_9") (pintype "bidirectional"))
    )
    (net (code "169") (name "unconnected-(IC11-2~{CLR}-Pad13)") (class "Default")
      (node (ref "IC11") (pin "13") (pinfunction "2~{CLR}_13") (pintype "bidirectional"))
    )
    (net (code "170") (name "unconnected-(IC11-2~{PRE}-Pad10)") (class "Default")
      (node (ref "IC11") (pin "10") (pinfunction "2~{PRE}_10") (pintype "bidirectional"))
    )
    (net (code "171") (name "unconnected-(IC11-2~{Q}-Pad8)") (class "Default")
      (node (ref "IC11") (pin "8") (pinfunction "2~{Q}_8") (pintype "bidirectional"))
    )
    (net (code "172") (name "unconnected-(IC14-~{QH}-Pad7)") (class "Default")
      (node (ref "IC14") (pin "7") (pinfunction "~{QH}_7") (pintype "bidirectional"))
    )
    (net (code "173") (name "unconnected-(IC15-~{QH}-Pad7)") (class "Default")
      (node (ref "IC15") (pin "7") (pinfunction "~{QH}_7") (pintype "bidirectional"))
    )
    (net (code "174") (name "unconnected-(IC16-~{QH}-Pad7)") (class "Default")
      (node (ref "IC16") (pin "7") (pinfunction "~{QH}_7") (pintype "bidirectional"))
    )
    (net (code "175") (name "unconnected-(IC17-SER-Pad10)") (class "Default")
      (node (ref "IC17") (pin "10") (pinfunction "SER_10") (pintype "bidirectional"))
    )
    (net (code "176") (name "unconnected-(IC17-~{QH}-Pad7)") (class "Default")
      (node (ref "IC17") (pin "7") (pinfunction "~{QH}_7") (pintype "bidirectional"))
    )
    (net (code "177") (name "unconnected-(J3-Pad2)") (class "Default")
      (node (ref "J3") (pin "2") (pinfunction "2_2") (pintype "bidirectional"))
    )
    (net (code "178") (name "unconnected-(J4-Pad2)") (class "Default")
      (node (ref "J4") (pin "2") (pinfunction "2_2") (pintype "bidirectional"))
    )
    (net (code "179") (name "unconnected-(J5-Pad6)") (class "Default")
      (node (ref "J5") (pin "6") (pinfunction "6_6") (pintype "bidirectional"))
    )
    (net (code "180") (name "unconnected-(J6-Pad5)") (class "Default")
      (node (ref "J6") (pin "5") (pinfunction "5_5") (pintype "bidirectional"))
    )
    (net (code "181") (name "unconnected-(J7-Pad4)") (class "Default")
      (node (ref "J7") (pin "4") (pinfunction "4_4") (pintype "bidirectional"))
    )
    (net (code "182") (name "unconnected-(J8-Pad3)") (class "Default")
      (node (ref "J8") (pin "3") (pinfunction "3_3") (pintype "bidirectional"))
    )
    (net (code "183") (name "unconnected-(J9-Pad7)") (class "Default")
      (node (ref "J9") (pin "7") (pinfunction "7_7") (pintype "bidirectional"))
    )
    (net (code "184") (name "unconnected-(JP1-Pad1)") (class "Default")
      (node (ref "JP1") (pin "1") (pinfunction "1_1") (pintype "passive"))
    )
    (net (code "185") (name "unconnected-(JP1-Pad2)") (class "Default")
      (node (ref "JP1") (pin "2") (pinfunction "2_2") (pintype "passive"))
    )
    (net (code "186") (name "unconnected-(JP1-Pad3)") (class "Default")
      (node (ref "JP1") (pin "3") (pinfunction "3_3") (pintype "passive"))
    )
    (net (code "187") (name "unconnected-(JP1-Pad4)") (class "Default")
      (node (ref "JP1") (pin "4") (pinfunction "4_4") (pintype "passive"))
    )
    (net (code "188") (name "unconnected-(JP1-Pad5)") (class "Default")
      (node (ref "JP1") (pin "5") (pinfunction "5_5") (pintype "passive"))
    )
    (net (code "189") (name "unconnected-(JP2-Pad2)") (class "Default")
      (node (ref "JP2") (pin "2") (pinfunction "2_2") (pintype "passive"))
    )
    (net (code "190") (name "unconnected-(JP3-Pad1)") (class "Default")
      (node (ref "JP3") (pin "1") (pinfunction "1_1") (pintype "passive"))
    )
    (net (code "191") (name "unconnected-(JP3-Pad3)") (class "Default")
      (node (ref "JP3") (pin "3") (pinfunction "3_3") (pintype "passive"))
    )
    (net (code "192") (name "unconnected-(JP3-Pad4)") (class "Default")
      (node (ref "JP3") (pin "4") (pinfunction "4_4") (pintype "passive"))
    )
    (net (code "193") (name "unconnected-(JP3-Pad6)") (class "Default")
      (node (ref "JP3") (pin "6") (pinfunction "6_6") (pintype "passive"))
    )
    (net (code "194") (name "unconnected-(JP5-Pad3)") (class "Default")
      (node (ref "JP5") (pin "3") (pinfunction "3_3") (pintype "passive"))
    )
    (net (code "195") (name "unconnected-(JP5-Pad4)") (class "Default")
      (node (ref "JP5") (pin "4") (pinfunction "4_4") (pintype "passive"))
    )
    (net (code "196") (name "unconnected-(JP5-Pad8)") (class "Default")
      (node (ref "JP5") (pin "8") (pinfunction "8_8") (pintype "passive"))
    )
    (net (code "197") (name "unconnected-(PICO1-Pad3V3_EN)") (class "Default")
      (node (ref "PICO1") (pin "3V3_EN") (pinfunction "3V3_EN_3V3_EN") (pintype "bidirectional"))
    )
    (net (code "198") (name "unconnected-(PICO1-PadADC_VREF)") (class "Default")
      (node (ref "PICO1") (pin "ADC_VREF") (pinfunction "ADC_VREF_ADC_VREF") (pintype "bidirectional"))
    )
    (net (code "199") (name "unconnected-(PICO1-PadGP21)") (class "Default")
      (node (ref "PICO1") (pin "GP21") (pinfunction "GP21_GP21") (pintype "bidirectional"))
    )
    (net (code "200") (name "unconnected-(PICO1-PadVSYS)") (class "Default")
      (node (ref "PICO1") (pin "VSYS") (pinfunction "VSYS_VSYS") (pintype "bidirectional"))
    )
    (net (code "201") (name "unconnected-(PICO2-Pad3V3_EN)") (class "Default")
      (node (ref "PICO2") (pin "3V3_EN") (pinfunction "3V3_EN_3V3_EN") (pintype "bidirectional"))
    )
    (net (code "202") (name "unconnected-(PICO2-PadADC_VREF)") (class "Default")
      (node (ref "PICO2") (pin "ADC_VREF") (pinfunction "ADC_VREF_ADC_VREF") (pintype "bidirectional"))
    )
    (net (code "203") (name "unconnected-(PICO2-PadAGND)") (class "Default")
      (node (ref "PICO2") (pin "AGND") (pinfunction "AGND_AGND") (pintype "bidirectional"))
    )
    (net (code "204") (name "unconnected-(PICO2-PadVBUS)") (class "Default")
      (node (ref "PICO2") (pin "VBUS") (pinfunction "VBUS_VBUS") (pintype "bidirectional"))
    )
    (net (code "205") (name "{slash}PERIPHERAL_POWER_ENABLE") (class "Default")
      (node (ref "J14") (pin "7") (pinfunction "7_7") (pintype "bidirectional"))
      (node (ref "PICO1") (pin "GP5") (pinfunction "GP5_GP5") (pintype "bidirectional"))
      (node (ref "R26") (pin "1") (pinfunction "1_1") (pintype "passive"))
      (node (ref "R28") (pin "1") (pinfunction "1_1") (pintype "passive"))
      (node (ref "R33") (pin "1") (pinfunction "1_1") (pintype "passive"))
    )
  )
)
